# MyNixie.net
KiCad netlist of a schematic drawn in Altium Designer
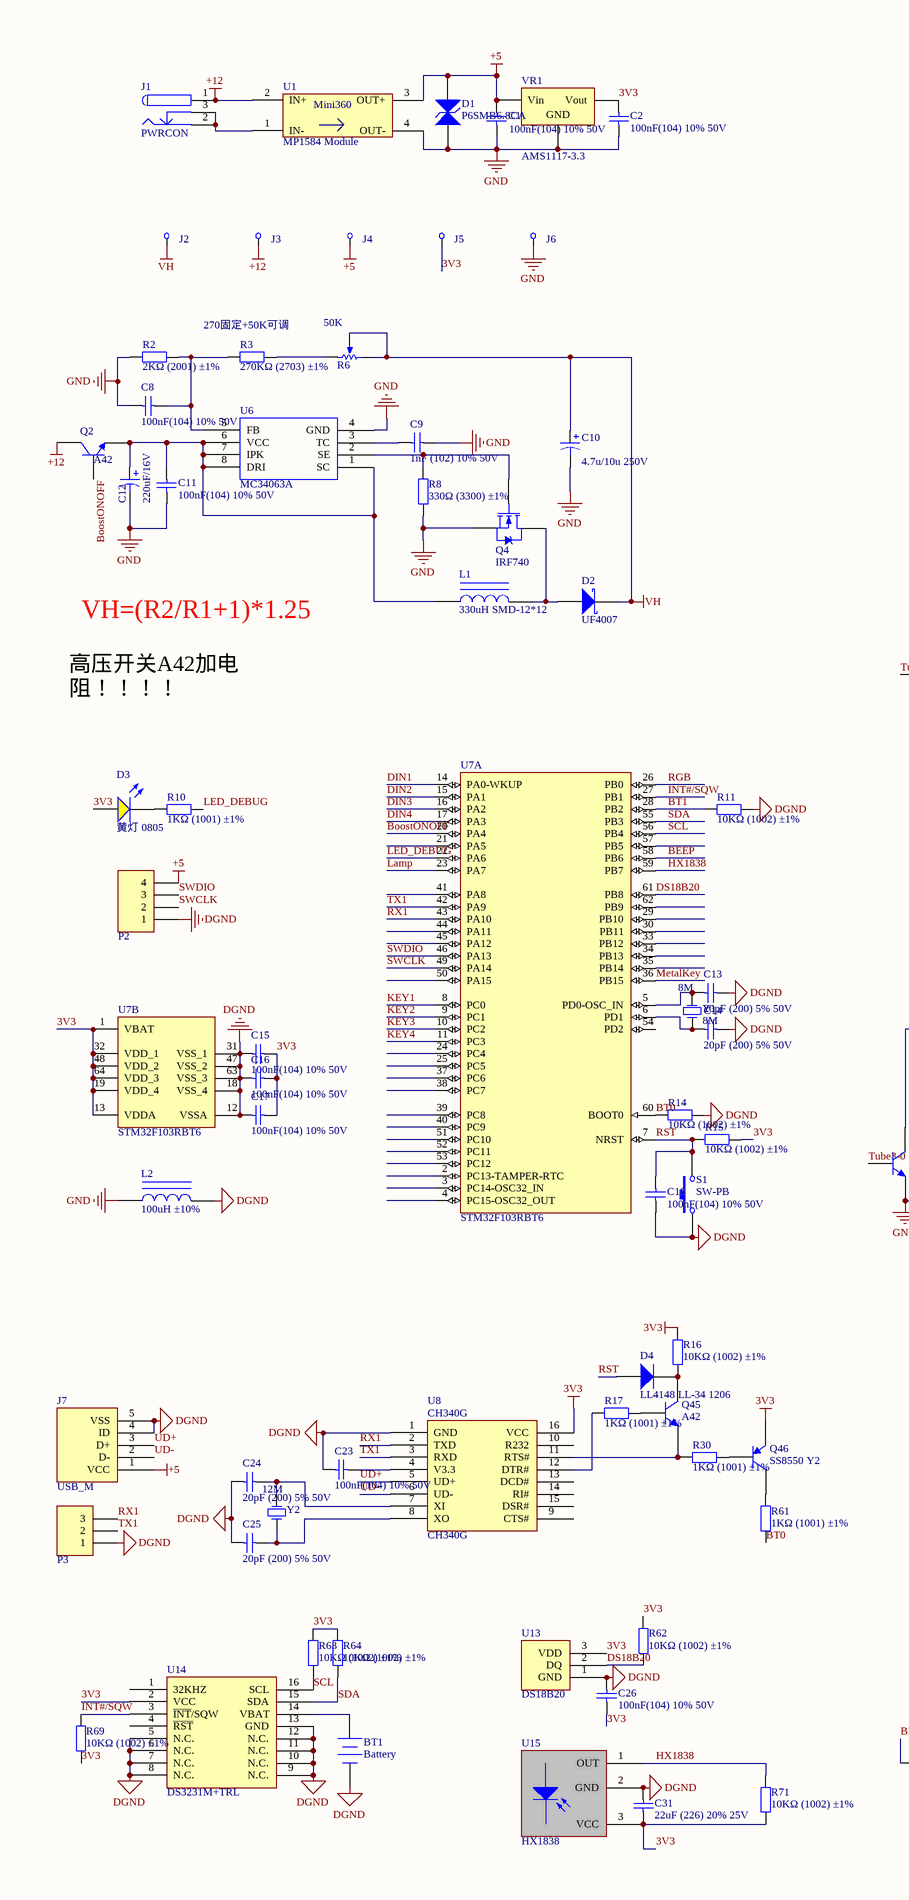
[diagram p0: MyNixie.SchDoc, left]
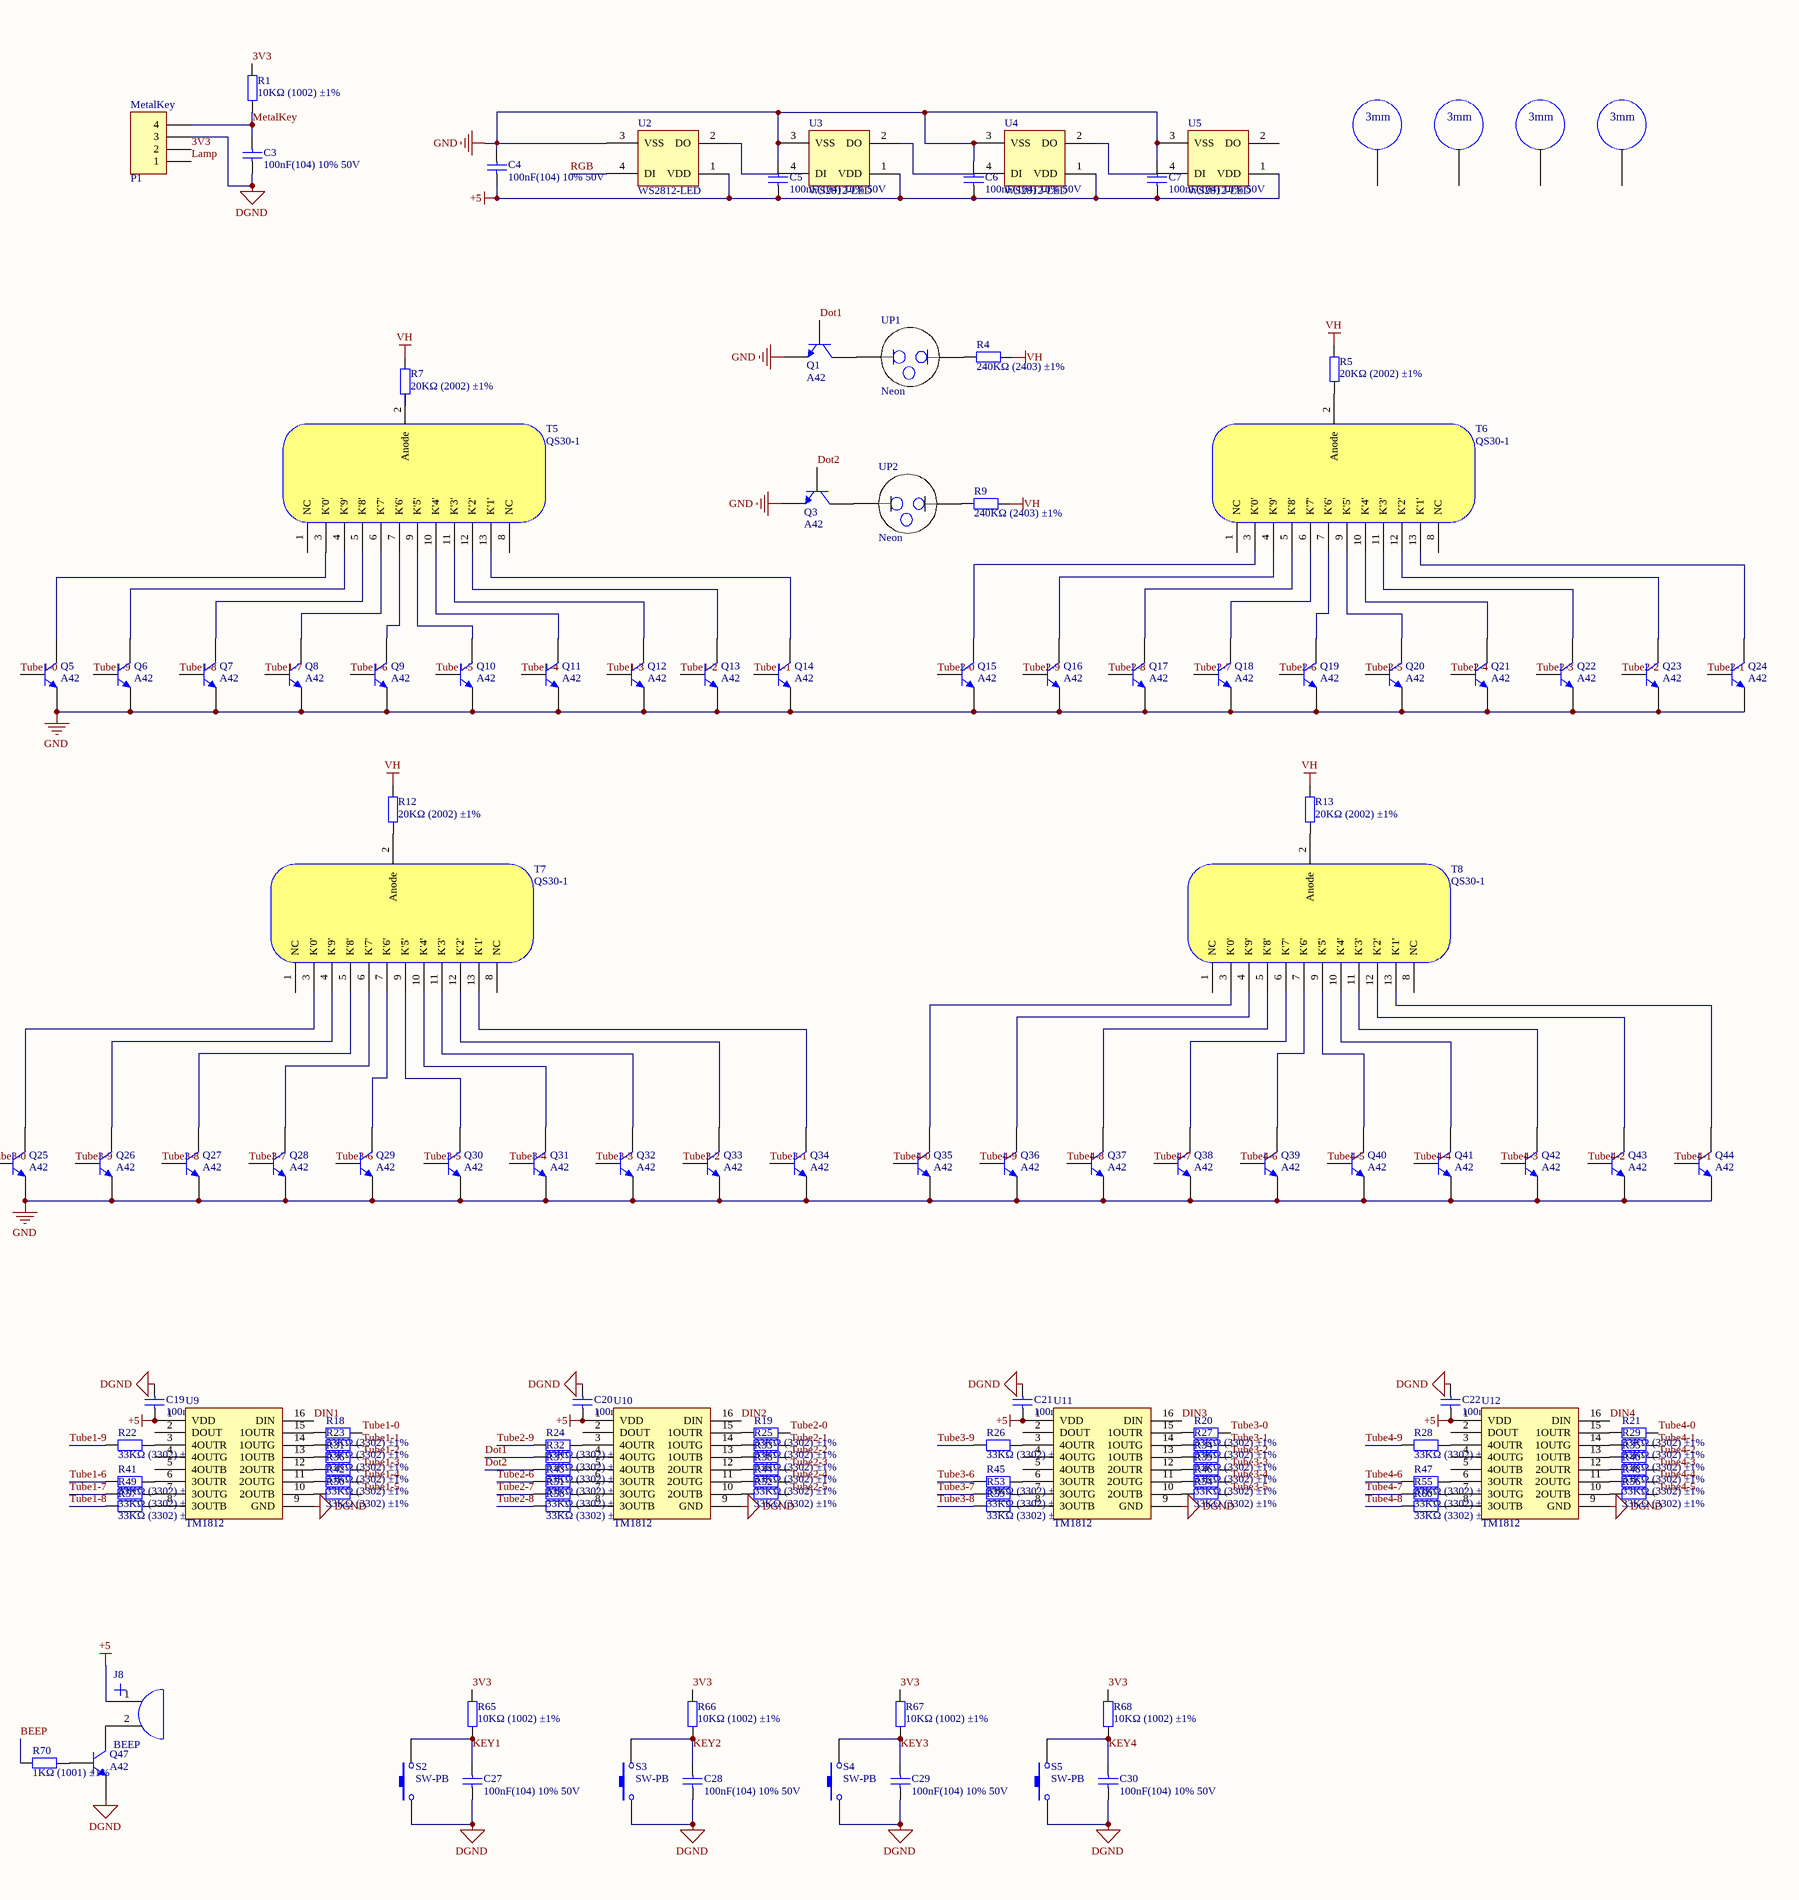
[diagram p1: MyNixie.SchDoc, right]

(export (version "E")
  (design (tool "Eeschema 10.0.6"))
  (components
    (comp (ref "BT1")
      (value "Battery")
      (footprint "CR2032")
      (description "备份电池")
      (fields (field (name "PUBLISHER") "Altium Limited"))
      (libsource (lib "fszhang") (part "Battery"))
    )
    (comp (ref "C1")
      (value "100nF(104) 10% 50V")
      (footprint "LC-0805_C")
      (description "贴片电容")
      (libsource (lib "Miscellaneous Devices LC") (part "0805 100nF(104) 10% 50V"))
    )
    (comp (ref "C2")
      (value "100nF(104) 10% 50V")
      (footprint "LC-0805_C")
      (description "贴片电容")
      (libsource (lib "Miscellaneous Devices LC") (part "0805 100nF(104) 10% 50V"))
    )
    (comp (ref "C3")
      (value "100nF(104) 10% 50V")
      (footprint "LC-0805_C")
      (description "贴片电容")
      (libsource (lib "Miscellaneous Devices LC") (part "0805 100nF(104) 10% 50V"))
    )
    (comp (ref "C4")
      (value "100nF(104) 10% 50V")
      (footprint "LC-0805_C")
      (description "贴片电容")
      (libsource (lib "Miscellaneous Devices LC") (part "0805 100nF(104) 10% 50V"))
    )
    (comp (ref "C5")
      (value "100nF(104) 10% 50V")
      (footprint "LC-0805_C")
      (description "贴片电容")
      (libsource (lib "Miscellaneous Devices LC") (part "0805 100nF(104) 10% 50V"))
    )
    (comp (ref "C6")
      (value "100nF(104) 10% 50V")
      (footprint "LC-0805_C")
      (description "贴片电容")
      (libsource (lib "Miscellaneous Devices LC") (part "0805 100nF(104) 10% 50V"))
    )
    (comp (ref "C7")
      (value "100nF(104) 10% 50V")
      (footprint "LC-0805_C")
      (description "贴片电容")
      (libsource (lib "Miscellaneous Devices LC") (part "0805 100nF(104) 10% 50V"))
    )
    (comp (ref "C8")
      (value "100nF(104) 10% 50V")
      (footprint "LC-0805_C")
      (description "贴片电容")
      (libsource (lib "Miscellaneous Devices LC") (part "0805 100nF(104) 10% 50V"))
    )
    (comp (ref "C9")
      (value "1nF (102) 10% 50V")
      (footprint "LC-0805_C")
      (description "贴片电容")
      (libsource (lib "Miscellaneous Devices LC") (part "0805 1nF (102) 10% 50V"))
    )
    (comp (ref "C10")
      (value "4.7u/10u 250V")
      (footprint "C-RB-8")
      (description "极性电解电容")
      (fields (field (name "PUBLISHER") "Altium Limited"))
      (libsource (lib "Miscellaneous Devices") (part "Cap Pol1"))
    )
    (comp (ref "C11")
      (value "100nF(104) 10% 50V")
      (footprint "LC-0805_C")
      (description "贴片电容")
      (libsource (lib "Miscellaneous Devices LC") (part "0805 100nF(104) 10% 50V"))
    )
    (comp (ref "C12")
      (value "220uF/16V")
      (footprint "C-RB-6")
      (description "极性电解电容")
      (fields (field (name "PUBLISHER") "Altium Limited"))
      (libsource (lib "Miscellaneous Devices") (part "Cap Pol1"))
    )
    (comp (ref "C13")
      (value "20pF (200) 5% 50V")
      (footprint "LC-0805_C")
      (description "贴片电容")
      (libsource (lib "Miscellaneous Devices LC") (part "0805 20pF (200) 5% 50V"))
    )
    (comp (ref "C14")
      (value "20pF (200) 5% 50V")
      (footprint "LC-0805_C")
      (description "贴片电容")
      (libsource (lib "Miscellaneous Devices LC") (part "0805 20pF (200) 5% 50V"))
    )
    (comp (ref "C15")
      (value "100nF(104) 10% 50V")
      (footprint "LC-0805_C")
      (description "贴片电容")
      (libsource (lib "Miscellaneous Devices LC") (part "0805 100nF(104) 10% 50V"))
    )
    (comp (ref "C16")
      (value "100nF(104) 10% 50V")
      (footprint "LC-0805_C")
      (description "贴片电容")
      (libsource (lib "Miscellaneous Devices LC") (part "0805 100nF(104) 10% 50V"))
    )
    (comp (ref "C17")
      (value "100nF(104) 10% 50V")
      (footprint "LC-0805_C")
      (description "贴片电容")
      (libsource (lib "Miscellaneous Devices LC") (part "0805 100nF(104) 10% 50V"))
    )
    (comp (ref "C18")
      (value "100nF(104) 10% 50V")
      (footprint "LC-0805_C")
      (description "贴片电容")
      (libsource (lib "Miscellaneous Devices LC") (part "0805 100nF(104) 10% 50V"))
    )
    (comp (ref "C19")
      (value "100nF(104) 10% 50V")
      (footprint "LC-0805_C")
      (description "贴片电容")
      (libsource (lib "Miscellaneous Devices LC") (part "0805 100nF(104) 10% 50V"))
    )
    (comp (ref "C20")
      (value "100nF(104) 10% 50V")
      (footprint "LC-0805_C")
      (description "贴片电容")
      (libsource (lib "Miscellaneous Devices LC") (part "0805 100nF(104) 10% 50V"))
    )
    (comp (ref "C21")
      (value "100nF(104) 10% 50V")
      (footprint "LC-0805_C")
      (description "贴片电容")
      (libsource (lib "Miscellaneous Devices LC") (part "0805 100nF(104) 10% 50V"))
    )
    (comp (ref "C22")
      (value "100nF(104) 10% 50V")
      (footprint "LC-0805_C")
      (description "贴片电容")
      (libsource (lib "Miscellaneous Devices LC") (part "0805 100nF(104) 10% 50V"))
    )
    (comp (ref "C23")
      (value "100nF(104) 10% 50V")
      (footprint "LC-0805_C")
      (description "贴片电容")
      (libsource (lib "Miscellaneous Devices LC") (part "0805 100nF(104) 10% 50V"))
    )
    (comp (ref "C24")
      (value "20pF (200) 5% 50V")
      (footprint "LC-0805_C")
      (description "贴片电容")
      (libsource (lib "Miscellaneous Devices LC") (part "0805 20pF (200) 5% 50V"))
    )
    (comp (ref "C25")
      (value "20pF (200) 5% 50V")
      (footprint "LC-0805_C")
      (description "贴片电容")
      (libsource (lib "Miscellaneous Devices LC") (part "0805 20pF (200) 5% 50V"))
    )
    (comp (ref "C26")
      (value "100nF(104) 10% 50V")
      (footprint "LC-0805_C")
      (description "贴片电容")
      (libsource (lib "Miscellaneous Devices LC") (part "0805 100nF(104) 10% 50V"))
    )
    (comp (ref "C27")
      (value "100nF(104) 10% 50V")
      (footprint "LC-0805_C")
      (description "贴片电容")
      (libsource (lib "Miscellaneous Devices LC") (part "0805 100nF(104) 10% 50V"))
    )
    (comp (ref "C28")
      (value "100nF(104) 10% 50V")
      (footprint "LC-0805_C")
      (description "贴片电容")
      (libsource (lib "Miscellaneous Devices LC") (part "0805 100nF(104) 10% 50V"))
    )
    (comp (ref "C29")
      (value "100nF(104) 10% 50V")
      (footprint "LC-0805_C")
      (description "贴片电容")
      (libsource (lib "Miscellaneous Devices LC") (part "0805 100nF(104) 10% 50V"))
    )
    (comp (ref "C30")
      (value "100nF(104) 10% 50V")
      (footprint "LC-0805_C")
      (description "贴片电容")
      (libsource (lib "Miscellaneous Devices LC") (part "0805 100nF(104) 10% 50V"))
    )
    (comp (ref "C31")
      (value "22uF (226) 20% 25V")
      (footprint "LC-0805_C")
      (description "贴片电容")
      (libsource (lib "Miscellaneous Devices LC") (part "0805 22uF (226) 20% 25V"))
    )
    (comp (ref "D1")
      (value "P6SMB6.8CA")
      (footprint "LC-SMB(DO-214AA)_S1")
      (description "TVS")
      (libsource (lib "Miscellaneous Devices LC") (part "SMB/DO-214AA P6SMB6.8CA"))
    )
    (comp (ref "D2")
      (value "UF4007")
      (footprint "DO-41")
      (description "Schottky Diode")
      (fields (field (name "PUBLISHER") "Altium Limited"))
      (libsource (lib "Miscellaneous Devices") (part "D Schottky"))
    )
    (comp (ref "D3")
      (value "黄灯 0805")
      (footprint "LC-0805_LED_S1")
      (description "发光二极管")
      (libsource (lib "Miscellaneous Devices LC") (part "0805 黄灯"))
    )
    (comp (ref "D4")
      (value "LL4148 LL-34 1206")
      (footprint "LC-LL-34")
      (description "开关二极管")
      (libsource (lib "Miscellaneous Devices LC") (part "LL-34 LL4148 LL-34 1206"))
    )
    (comp (ref "J1")
      (value "PWRCON")
      (footprint "DC-005")
      (description "直流电源端子")
      (fields (field (name "PUBLISHER") "Altium Limited"))
      (libsource (lib "fszhang") (part "PWRCON"))
    )
    (comp (ref "J2")
      (value "CHECK")
      (footprint "CHECK-B")
      (description "测试点")
      (libsource (lib "fszhang") (part "CHECK"))
    )
    (comp (ref "J3")
      (value "CHECK")
      (footprint "CHECK-B")
      (description "测试点")
      (libsource (lib "fszhang") (part "CHECK"))
    )
    (comp (ref "J4")
      (value "CHECK")
      (footprint "CHECK-B")
      (description "测试点")
      (libsource (lib "fszhang") (part "CHECK"))
    )
    (comp (ref "J5")
      (value "CHECK")
      (footprint "CHECK-B")
      (description "测试点")
      (libsource (lib "fszhang") (part "CHECK"))
    )
    (comp (ref "J6")
      (value "CHECK")
      (footprint "CHECK-B")
      (description "测试点")
      (libsource (lib "fszhang") (part "CHECK"))
    )
    (comp (ref "J7")
      (value "USB_M")
      (footprint "USB_MICRO")
      (description "MicroUSB接口")
      (libsource (lib "fszhang") (part "USB_M"))
    )
    (comp (ref "J8")
      (value "BEEP")
      (footprint "Beep")
      (description "蜂鸣器")
      (libsource (lib "fszhang") (part "BEEP"))
    )
    (comp (ref "L1")
      (value "330uH SMD-12*12")
      (footprint "L-SMD-12")
      (description "Magnetic-Core Inductor")
      (fields (field (name "PUBLISHER") "Altium Limited"))
      (libsource (lib "Miscellaneous Devices") (part "Inductor Iron"))
    )
    (comp (ref "L2")
      (value "100uH ±10%")
      (footprint "LC-0805_L")
      (description "贴片电感")
      (libsource (lib "Miscellaneous Devices LC") (part "0805 100uH 10%"))
    )
    (comp (ref "P1")
      (value "MetalKey")
      (footprint "HDR4X1_A")
      (description "接插件")
      (fields (field (name "PUBLISHER") "Altium Limited"))
      (libsource (lib "fszhang") (part "Header 4"))
    )
    (comp (ref "P2")
      (value "Header 4")
      (footprint "HDR4X1_A")
      (description "接插件")
      (fields (field (name "PUBLISHER") "Altium Limited"))
      (libsource (lib "fszhang") (part "Header 4"))
    )
    (comp (ref "P3")
      (value "Header 3")
      (footprint "HDR3X1_A")
      (description "接插件")
      (fields (field (name "PUBLISHER") "Altium Limited"))
      (libsource (lib "fszhang") (part "Header 3"))
    )
    (comp (ref "Q1")
      (value "A42")
      (footprint "LC-SOT-23(SOT-23-3)")
      (description "三极管")
      (libsource (lib "Miscellaneous Devices LC") (part "SOT-23 SS8050 Y1"))
    )
    (comp (ref "Q2")
      (value "A42")
      (footprint "LC-SOT-23(SOT-23-3)")
      (description "三极管")
      (libsource (lib "Miscellaneous Devices LC") (part "SOT-23 SS8050 Y1"))
    )
    (comp (ref "Q3")
      (value "A42")
      (footprint "LC-SOT-23(SOT-23-3)")
      (description "三极管")
      (libsource (lib "Miscellaneous Devices LC") (part "SOT-23 SS8050 Y1"))
    )
    (comp (ref "Q4")
      (value "IRF740")
      (footprint "TO-220AB")
      (description "N-Channel Power MOSFET")
      (fields (field (name "PUBLISHER") "Altium Limited"))
      (libsource (lib "Miscellaneous Devices") (part "NMOS-2"))
    )
    (comp (ref "Q5")
      (value "A42")
      (footprint "LC-SOT-23(SOT-23-3)")
      (description "三极管")
      (libsource (lib "Miscellaneous Devices LC") (part "SOT-23 SS8050 Y1"))
    )
    (comp (ref "Q6")
      (value "A42")
      (footprint "LC-SOT-23(SOT-23-3)")
      (description "三极管")
      (libsource (lib "Miscellaneous Devices LC") (part "SOT-23 SS8050 Y1"))
    )
    (comp (ref "Q7")
      (value "A42")
      (footprint "LC-SOT-23(SOT-23-3)")
      (description "三极管")
      (libsource (lib "Miscellaneous Devices LC") (part "SOT-23 SS8050 Y1"))
    )
    (comp (ref "Q8")
      (value "A42")
      (footprint "LC-SOT-23(SOT-23-3)")
      (description "三极管")
      (libsource (lib "Miscellaneous Devices LC") (part "SOT-23 SS8050 Y1"))
    )
    (comp (ref "Q9")
      (value "A42")
      (footprint "LC-SOT-23(SOT-23-3)")
      (description "三极管")
      (libsource (lib "Miscellaneous Devices LC") (part "SOT-23 SS8050 Y1"))
    )
    (comp (ref "Q10")
      (value "A42")
      (footprint "LC-SOT-23(SOT-23-3)")
      (description "三极管")
      (libsource (lib "Miscellaneous Devices LC") (part "SOT-23 SS8050 Y1"))
    )
    (comp (ref "Q11")
      (value "A42")
      (footprint "LC-SOT-23(SOT-23-3)")
      (description "三极管")
      (libsource (lib "Miscellaneous Devices LC") (part "SOT-23 SS8050 Y1"))
    )
    (comp (ref "Q12")
      (value "A42")
      (footprint "LC-SOT-23(SOT-23-3)")
      (description "三极管")
      (libsource (lib "Miscellaneous Devices LC") (part "SOT-23 SS8050 Y1"))
    )
    (comp (ref "Q13")
      (value "A42")
      (footprint "LC-SOT-23(SOT-23-3)")
      (description "三极管")
      (libsource (lib "Miscellaneous Devices LC") (part "SOT-23 SS8050 Y1"))
    )
    (comp (ref "Q14")
      (value "A42")
      (footprint "LC-SOT-23(SOT-23-3)")
      (description "三极管")
      (libsource (lib "Miscellaneous Devices LC") (part "SOT-23 SS8050 Y1"))
    )
    (comp (ref "Q15")
      (value "A42")
      (footprint "LC-SOT-23(SOT-23-3)")
      (description "三极管")
      (libsource (lib "Miscellaneous Devices LC") (part "SOT-23 SS8050 Y1"))
    )
    (comp (ref "Q16")
      (value "A42")
      (footprint "LC-SOT-23(SOT-23-3)")
      (description "三极管")
      (libsource (lib "Miscellaneous Devices LC") (part "SOT-23 SS8050 Y1"))
    )
    (comp (ref "Q17")
      (value "A42")
      (footprint "LC-SOT-23(SOT-23-3)")
      (description "三极管")
      (libsource (lib "Miscellaneous Devices LC") (part "SOT-23 SS8050 Y1"))
    )
    (comp (ref "Q18")
      (value "A42")
      (footprint "LC-SOT-23(SOT-23-3)")
      (description "三极管")
      (libsource (lib "Miscellaneous Devices LC") (part "SOT-23 SS8050 Y1"))
    )
    (comp (ref "Q19")
      (value "A42")
      (footprint "LC-SOT-23(SOT-23-3)")
      (description "三极管")
      (libsource (lib "Miscellaneous Devices LC") (part "SOT-23 SS8050 Y1"))
    )
    (comp (ref "Q20")
      (value "A42")
      (footprint "LC-SOT-23(SOT-23-3)")
      (description "三极管")
      (libsource (lib "Miscellaneous Devices LC") (part "SOT-23 SS8050 Y1"))
    )
    (comp (ref "Q21")
      (value "A42")
      (footprint "LC-SOT-23(SOT-23-3)")
      (description "三极管")
      (libsource (lib "Miscellaneous Devices LC") (part "SOT-23 SS8050 Y1"))
    )
    (comp (ref "Q22")
      (value "A42")
      (footprint "LC-SOT-23(SOT-23-3)")
      (description "三极管")
      (libsource (lib "Miscellaneous Devices LC") (part "SOT-23 SS8050 Y1"))
    )
    (comp (ref "Q23")
      (value "A42")
      (footprint "LC-SOT-23(SOT-23-3)")
      (description "三极管")
      (libsource (lib "Miscellaneous Devices LC") (part "SOT-23 SS8050 Y1"))
    )
    (comp (ref "Q24")
      (value "A42")
      (footprint "LC-SOT-23(SOT-23-3)")
      (description "三极管")
      (libsource (lib "Miscellaneous Devices LC") (part "SOT-23 SS8050 Y1"))
    )
    (comp (ref "Q25")
      (value "A42")
      (footprint "LC-SOT-23(SOT-23-3)")
      (description "三极管")
      (libsource (lib "Miscellaneous Devices LC") (part "SOT-23 SS8050 Y1"))
    )
    (comp (ref "Q26")
      (value "A42")
      (footprint "LC-SOT-23(SOT-23-3)")
      (description "三极管")
      (libsource (lib "Miscellaneous Devices LC") (part "SOT-23 SS8050 Y1"))
    )
    (comp (ref "Q27")
      (value "A42")
      (footprint "LC-SOT-23(SOT-23-3)")
      (description "三极管")
      (libsource (lib "Miscellaneous Devices LC") (part "SOT-23 SS8050 Y1"))
    )
    (comp (ref "Q28")
      (value "A42")
      (footprint "LC-SOT-23(SOT-23-3)")
      (description "三极管")
      (libsource (lib "Miscellaneous Devices LC") (part "SOT-23 SS8050 Y1"))
    )
    (comp (ref "Q29")
      (value "A42")
      (footprint "LC-SOT-23(SOT-23-3)")
      (description "三极管")
      (libsource (lib "Miscellaneous Devices LC") (part "SOT-23 SS8050 Y1"))
    )
    (comp (ref "Q30")
      (value "A42")
      (footprint "LC-SOT-23(SOT-23-3)")
      (description "三极管")
      (libsource (lib "Miscellaneous Devices LC") (part "SOT-23 SS8050 Y1"))
    )
    (comp (ref "Q31")
      (value "A42")
      (footprint "LC-SOT-23(SOT-23-3)")
      (description "三极管")
      (libsource (lib "Miscellaneous Devices LC") (part "SOT-23 SS8050 Y1"))
    )
    (comp (ref "Q32")
      (value "A42")
      (footprint "LC-SOT-23(SOT-23-3)")
      (description "三极管")
      (libsource (lib "Miscellaneous Devices LC") (part "SOT-23 SS8050 Y1"))
    )
    (comp (ref "Q33")
      (value "A42")
      (footprint "LC-SOT-23(SOT-23-3)")
      (description "三极管")
      (libsource (lib "Miscellaneous Devices LC") (part "SOT-23 SS8050 Y1"))
    )
    (comp (ref "Q34")
      (value "A42")
      (footprint "LC-SOT-23(SOT-23-3)")
      (description "三极管")
      (libsource (lib "Miscellaneous Devices LC") (part "SOT-23 SS8050 Y1"))
    )
    (comp (ref "Q35")
      (value "A42")
      (footprint "LC-SOT-23(SOT-23-3)")
      (description "三极管")
      (libsource (lib "Miscellaneous Devices LC") (part "SOT-23 SS8050 Y1"))
    )
    (comp (ref "Q36")
      (value "A42")
      (footprint "LC-SOT-23(SOT-23-3)")
      (description "三极管")
      (libsource (lib "Miscellaneous Devices LC") (part "SOT-23 SS8050 Y1"))
    )
    (comp (ref "Q37")
      (value "A42")
      (footprint "LC-SOT-23(SOT-23-3)")
      (description "三极管")
      (libsource (lib "Miscellaneous Devices LC") (part "SOT-23 SS8050 Y1"))
    )
    (comp (ref "Q38")
      (value "A42")
      (footprint "LC-SOT-23(SOT-23-3)")
      (description "三极管")
      (libsource (lib "Miscellaneous Devices LC") (part "SOT-23 SS8050 Y1"))
    )
    (comp (ref "Q39")
      (value "A42")
      (footprint "LC-SOT-23(SOT-23-3)")
      (description "三极管")
      (libsource (lib "Miscellaneous Devices LC") (part "SOT-23 SS8050 Y1"))
    )
    (comp (ref "Q40")
      (value "A42")
      (footprint "LC-SOT-23(SOT-23-3)")
      (description "三极管")
      (libsource (lib "Miscellaneous Devices LC") (part "SOT-23 SS8050 Y1"))
    )
    (comp (ref "Q41")
      (value "A42")
      (footprint "LC-SOT-23(SOT-23-3)")
      (description "三极管")
      (libsource (lib "Miscellaneous Devices LC") (part "SOT-23 SS8050 Y1"))
    )
    (comp (ref "Q42")
      (value "A42")
      (footprint "LC-SOT-23(SOT-23-3)")
      (description "三极管")
      (libsource (lib "Miscellaneous Devices LC") (part "SOT-23 SS8050 Y1"))
    )
    (comp (ref "Q43")
      (value "A42")
      (footprint "LC-SOT-23(SOT-23-3)")
      (description "三极管")
      (libsource (lib "Miscellaneous Devices LC") (part "SOT-23 SS8050 Y1"))
    )
    (comp (ref "Q44")
      (value "A42")
      (footprint "LC-SOT-23(SOT-23-3)")
      (description "三极管")
      (libsource (lib "Miscellaneous Devices LC") (part "SOT-23 SS8050 Y1"))
    )
    (comp (ref "Q45")
      (value "A42")
      (footprint "LC-SOT-23(SOT-23-3)")
      (description "三极管")
      (libsource (lib "Miscellaneous Devices LC") (part "SOT-23 SS8050 Y1"))
    )
    (comp (ref "Q46")
      (value "SS8550 Y2")
      (footprint "LC-SOT-23(SOT-23-3)")
      (description "三极管")
      (libsource (lib "Miscellaneous Devices LC") (part "SOT-23 SS8550 Y2"))
    )
    (comp (ref "Q47")
      (value "A42")
      (footprint "LC-SOT-23(SOT-23-3)")
      (description "三极管")
      (libsource (lib "Miscellaneous Devices LC") (part "SOT-23 SS8050 Y1"))
    )
    (comp (ref "R1")
      (value "10KΩ (1002) ±1%")
      (footprint "LC-0805_R")
      (description "贴片电阻")
      (libsource (lib "") (part "0805 10KΩ (1002) 1%_2"))
    )
    (comp (ref "R2")
      (value "2KΩ (2001) ±1%")
      (footprint "LC-0805_R")
      (description "贴片电阻")
      (libsource (lib "Miscellaneous Devices LC") (part "0805 2KΩ (2001) 1%"))
    )
    (comp (ref "R3")
      (value "270KΩ (2703) ±1%")
      (footprint "LC-0805_R")
      (description "贴片电阻")
      (libsource (lib "Miscellaneous Devices LC") (part "0805 270KΩ (2703) 1%"))
    )
    (comp (ref "R4")
      (value "240KΩ (2403) ±1%")
      (footprint "LC-0805_R")
      (description "贴片电阻")
      (libsource (lib "Miscellaneous Devices LC") (part "0805 240KΩ (2403) 1%"))
    )
    (comp (ref "R5")
      (value "20KΩ (2002) ±1%")
      (footprint "LC-0805_R")
      (description "贴片电阻")
      (libsource (lib "Miscellaneous Devices LC") (part "0805 20KΩ (2002) 1%"))
    )
    (comp (ref "R6")
      (value "50K")
      (footprint "VR_B1")
      (description "精密可调电阻")
      (fields (field (name "PUBLISHER") "Altium Limited"))
      (libsource (lib "fszhang") (part "RES-RPot"))
    )
    (comp (ref "R7")
      (value "20KΩ (2002) ±1%")
      (footprint "LC-0805_R")
      (description "贴片电阻")
      (libsource (lib "Miscellaneous Devices LC") (part "0805 20KΩ (2002) 1%"))
    )
    (comp (ref "R8")
      (value "330Ω (3300) ±1%")
      (footprint "LC-0805_R")
      (description "贴片电阻")
      (libsource (lib "Miscellaneous Devices LC") (part "0805 330Ω (3300) 1%"))
    )
    (comp (ref "R9")
      (value "240KΩ (2403) ±1%")
      (footprint "LC-0805_R")
      (description "贴片电阻")
      (libsource (lib "Miscellaneous Devices LC") (part "0805 240KΩ (2403) 1%"))
    )
    (comp (ref "R10")
      (value "1KΩ (1001) ±1%")
      (footprint "LC-0805_R")
      (description "贴片电阻")
      (libsource (lib "") (part "0805 1KΩ (1001) 1%_1"))
    )
    (comp (ref "R11")
      (value "10KΩ (1002) ±1%")
      (footprint "LC-0805_R")
      (description "贴片电阻")
      (libsource (lib "Miscellaneous Devices LC") (part "0805 10KΩ (1002) 1%"))
    )
    (comp (ref "R12")
      (value "20KΩ (2002) ±1%")
      (footprint "LC-0805_R")
      (description "贴片电阻")
      (libsource (lib "Miscellaneous Devices LC") (part "0805 20KΩ (2002) 1%"))
    )
    (comp (ref "R13")
      (value "20KΩ (2002) ±1%")
      (footprint "LC-0805_R")
      (description "贴片电阻")
      (libsource (lib "Miscellaneous Devices LC") (part "0805 20KΩ (2002) 1%"))
    )
    (comp (ref "R14")
      (value "10KΩ (1002) ±1%")
      (footprint "LC-0805_R")
      (description "贴片电阻")
      (libsource (lib "Miscellaneous Devices LC") (part "0805 10KΩ (1002) 1%"))
    )
    (comp (ref "R15")
      (value "10KΩ (1002) ±1%")
      (footprint "LC-0805_R")
      (description "贴片电阻")
      (libsource (lib "Miscellaneous Devices LC") (part "0805 10KΩ (1002) 1%"))
    )
    (comp (ref "R16")
      (value "10KΩ (1002) ±1%")
      (footprint "LC-0805_R")
      (description "贴片电阻")
      (libsource (lib "") (part "0805 10KΩ (1002) 1%_1"))
    )
    (comp (ref "R17")
      (value "1KΩ (1001) ±1%")
      (footprint "LC-0805_R")
      (description "贴片电阻")
      (libsource (lib "") (part "0805 1KΩ (1001) 1%_1"))
    )
    (comp (ref "R18")
      (value "33KΩ (3302) ±1%")
      (footprint "LC-0805_R")
      (description "贴片电阻")
      (libsource (lib "Miscellaneous Devices LC") (part "0805 33KΩ (3302) 1%"))
    )
    (comp (ref "R19")
      (value "33KΩ (3302) ±1%")
      (footprint "LC-0805_R")
      (description "贴片电阻")
      (libsource (lib "Miscellaneous Devices LC") (part "0805 33KΩ (3302) 1%"))
    )
    (comp (ref "R20")
      (value "33KΩ (3302) ±1%")
      (footprint "LC-0805_R")
      (description "贴片电阻")
      (libsource (lib "Miscellaneous Devices LC") (part "0805 33KΩ (3302) 1%"))
    )
    (comp (ref "R21")
      (value "33KΩ (3302) ±1%")
      (footprint "LC-0805_R")
      (description "贴片电阻")
      (libsource (lib "Miscellaneous Devices LC") (part "0805 33KΩ (3302) 1%"))
    )
    (comp (ref "R22")
      (value "33KΩ (3302) ±1%")
      (footprint "LC-0805_R")
      (description "贴片电阻")
      (libsource (lib "Miscellaneous Devices LC") (part "0805 33KΩ (3302) 1%"))
    )
    (comp (ref "R23")
      (value "33KΩ (3302) ±1%")
      (footprint "LC-0805_R")
      (description "贴片电阻")
      (libsource (lib "Miscellaneous Devices LC") (part "0805 33KΩ (3302) 1%"))
    )
    (comp (ref "R24")
      (value "33KΩ (3302) ±1%")
      (footprint "LC-0805_R")
      (description "贴片电阻")
      (libsource (lib "Miscellaneous Devices LC") (part "0805 33KΩ (3302) 1%"))
    )
    (comp (ref "R25")
      (value "33KΩ (3302) ±1%")
      (footprint "LC-0805_R")
      (description "贴片电阻")
      (libsource (lib "Miscellaneous Devices LC") (part "0805 33KΩ (3302) 1%"))
    )
    (comp (ref "R26")
      (value "33KΩ (3302) ±1%")
      (footprint "LC-0805_R")
      (description "贴片电阻")
      (libsource (lib "Miscellaneous Devices LC") (part "0805 33KΩ (3302) 1%"))
    )
    (comp (ref "R27")
      (value "33KΩ (3302) ±1%")
      (footprint "LC-0805_R")
      (description "贴片电阻")
      (libsource (lib "Miscellaneous Devices LC") (part "0805 33KΩ (3302) 1%"))
    )
    (comp (ref "R28")
      (value "33KΩ (3302) ±1%")
      (footprint "LC-0805_R")
      (description "贴片电阻")
      (libsource (lib "Miscellaneous Devices LC") (part "0805 33KΩ (3302) 1%"))
    )
    (comp (ref "R29")
      (value "33KΩ (3302) ±1%")
      (footprint "LC-0805_R")
      (description "贴片电阻")
      (libsource (lib "Miscellaneous Devices LC") (part "0805 33KΩ (3302) 1%"))
    )
    (comp (ref "R30")
      (value "1KΩ (1001) ±1%")
      (footprint "LC-0805_R")
      (description "贴片电阻")
      (libsource (lib "") (part "0805 1KΩ (1001) 1%_1"))
    )
    (comp (ref "R31")
      (value "33KΩ (3302) ±1%")
      (footprint "LC-0805_R")
      (description "贴片电阻")
      (libsource (lib "Miscellaneous Devices LC") (part "0805 33KΩ (3302) 1%"))
    )
    (comp (ref "R32")
      (value "33KΩ (3302) ±1%")
      (footprint "LC-0805_R")
      (description "贴片电阻")
      (libsource (lib "Miscellaneous Devices LC") (part "0805 33KΩ (3302) 1%"))
    )
    (comp (ref "R33")
      (value "33KΩ (3302) ±1%")
      (footprint "LC-0805_R")
      (description "贴片电阻")
      (libsource (lib "Miscellaneous Devices LC") (part "0805 33KΩ (3302) 1%"))
    )
    (comp (ref "R34")
      (value "33KΩ (3302) ±1%")
      (footprint "LC-0805_R")
      (description "贴片电阻")
      (libsource (lib "Miscellaneous Devices LC") (part "0805 33KΩ (3302) 1%"))
    )
    (comp (ref "R35")
      (value "33KΩ (3302) ±1%")
      (footprint "LC-0805_R")
      (description "贴片电阻")
      (libsource (lib "Miscellaneous Devices LC") (part "0805 33KΩ (3302) 1%"))
    )
    (comp (ref "R36")
      (value "33KΩ (3302) ±1%")
      (footprint "LC-0805_R")
      (description "贴片电阻")
      (libsource (lib "Miscellaneous Devices LC") (part "0805 33KΩ (3302) 1%"))
    )
    (comp (ref "R37")
      (value "33KΩ (3302) ±1%")
      (footprint "LC-0805_R")
      (description "贴片电阻")
      (libsource (lib "Miscellaneous Devices LC") (part "0805 33KΩ (3302) 1%"))
    )
    (comp (ref "R38")
      (value "33KΩ (3302) ±1%")
      (footprint "LC-0805_R")
      (description "贴片电阻")
      (libsource (lib "Miscellaneous Devices LC") (part "0805 33KΩ (3302) 1%"))
    )
    (comp (ref "R39")
      (value "33KΩ (3302) ±1%")
      (footprint "LC-0805_R")
      (description "贴片电阻")
      (libsource (lib "Miscellaneous Devices LC") (part "0805 33KΩ (3302) 1%"))
    )
    (comp (ref "R40")
      (value "33KΩ (3302) ±1%")
      (footprint "LC-0805_R")
      (description "贴片电阻")
      (libsource (lib "Miscellaneous Devices LC") (part "0805 33KΩ (3302) 1%"))
    )
    (comp (ref "R41")
      (value "33KΩ (3302) ±1%")
      (footprint "LC-0805_R")
      (description "贴片电阻")
      (libsource (lib "Miscellaneous Devices LC") (part "0805 33KΩ (3302) 1%"))
    )
    (comp (ref "R42")
      (value "33KΩ (3302) ±1%")
      (footprint "LC-0805_R")
      (description "贴片电阻")
      (libsource (lib "Miscellaneous Devices LC") (part "0805 33KΩ (3302) 1%"))
    )
    (comp (ref "R43")
      (value "33KΩ (3302) ±1%")
      (footprint "LC-0805_R")
      (description "贴片电阻")
      (libsource (lib "Miscellaneous Devices LC") (part "0805 33KΩ (3302) 1%"))
    )
    (comp (ref "R44")
      (value "33KΩ (3302) ±1%")
      (footprint "LC-0805_R")
      (description "贴片电阻")
      (libsource (lib "Miscellaneous Devices LC") (part "0805 33KΩ (3302) 1%"))
    )
    (comp (ref "R45")
      (value "33KΩ (3302) ±1%")
      (footprint "LC-0805_R")
      (description "贴片电阻")
      (libsource (lib "Miscellaneous Devices LC") (part "0805 33KΩ (3302) 1%"))
    )
    (comp (ref "R46")
      (value "33KΩ (3302) ±1%")
      (footprint "LC-0805_R")
      (description "贴片电阻")
      (libsource (lib "Miscellaneous Devices LC") (part "0805 33KΩ (3302) 1%"))
    )
    (comp (ref "R47")
      (value "33KΩ (3302) ±1%")
      (footprint "LC-0805_R")
      (description "贴片电阻")
      (libsource (lib "Miscellaneous Devices LC") (part "0805 33KΩ (3302) 1%"))
    )
    (comp (ref "R48")
      (value "33KΩ (3302) ±1%")
      (footprint "LC-0805_R")
      (description "贴片电阻")
      (libsource (lib "Miscellaneous Devices LC") (part "0805 33KΩ (3302) 1%"))
    )
    (comp (ref "R49")
      (value "33KΩ (3302) ±1%")
      (footprint "LC-0805_R")
      (description "贴片电阻")
      (libsource (lib "Miscellaneous Devices LC") (part "0805 33KΩ (3302) 1%"))
    )
    (comp (ref "R50")
      (value "33KΩ (3302) ±1%")
      (footprint "LC-0805_R")
      (description "贴片电阻")
      (libsource (lib "Miscellaneous Devices LC") (part "0805 33KΩ (3302) 1%"))
    )
    (comp (ref "R51")
      (value "33KΩ (3302) ±1%")
      (footprint "LC-0805_R")
      (description "贴片电阻")
      (libsource (lib "Miscellaneous Devices LC") (part "0805 33KΩ (3302) 1%"))
    )
    (comp (ref "R52")
      (value "33KΩ (3302) ±1%")
      (footprint "LC-0805_R")
      (description "贴片电阻")
      (libsource (lib "Miscellaneous Devices LC") (part "0805 33KΩ (3302) 1%"))
    )
    (comp (ref "R53")
      (value "33KΩ (3302) ±1%")
      (footprint "LC-0805_R")
      (description "贴片电阻")
      (libsource (lib "Miscellaneous Devices LC") (part "0805 33KΩ (3302) 1%"))
    )
    (comp (ref "R54")
      (value "33KΩ (3302) ±1%")
      (footprint "LC-0805_R")
      (description "贴片电阻")
      (libsource (lib "Miscellaneous Devices LC") (part "0805 33KΩ (3302) 1%"))
    )
    (comp (ref "R55")
      (value "33KΩ (3302) ±1%")
      (footprint "LC-0805_R")
      (description "贴片电阻")
      (libsource (lib "Miscellaneous Devices LC") (part "0805 33KΩ (3302) 1%"))
    )
    (comp (ref "R56")
      (value "33KΩ (3302) ±1%")
      (footprint "LC-0805_R")
      (description "贴片电阻")
      (libsource (lib "Miscellaneous Devices LC") (part "0805 33KΩ (3302) 1%"))
    )
    (comp (ref "R57")
      (value "33KΩ (3302) ±1%")
      (footprint "LC-0805_R")
      (description "贴片电阻")
      (libsource (lib "Miscellaneous Devices LC") (part "0805 33KΩ (3302) 1%"))
    )
    (comp (ref "R58")
      (value "33KΩ (3302) ±1%")
      (footprint "LC-0805_R")
      (description "贴片电阻")
      (libsource (lib "Miscellaneous Devices LC") (part "0805 33KΩ (3302) 1%"))
    )
    (comp (ref "R59")
      (value "33KΩ (3302) ±1%")
      (footprint "LC-0805_R")
      (description "贴片电阻")
      (libsource (lib "Miscellaneous Devices LC") (part "0805 33KΩ (3302) 1%"))
    )
    (comp (ref "R60")
      (value "33KΩ (3302) ±1%")
      (footprint "LC-0805_R")
      (description "贴片电阻")
      (libsource (lib "Miscellaneous Devices LC") (part "0805 33KΩ (3302) 1%"))
    )
    (comp (ref "R61")
      (value "1KΩ (1001) ±1%")
      (footprint "LC-0805_R")
      (description "贴片电阻")
      (libsource (lib "Miscellaneous Devices LC") (part "0805 1KΩ (1001) 1%"))
    )
    (comp (ref "R62")
      (value "10KΩ (1002) ±1%")
      (footprint "LC-0805_R")
      (description "贴片电阻")
      (libsource (lib "Miscellaneous Devices LC") (part "0805 10KΩ (1002) 1%"))
    )
    (comp (ref "R63")
      (value "10KΩ (1002) ±1%")
      (footprint "LC-0805_R")
      (description "贴片电阻")
      (libsource (lib "Miscellaneous Devices LC") (part "0805 10KΩ (1002) 1%"))
    )
    (comp (ref "R64")
      (value "10KΩ (1002) ±1%")
      (footprint "LC-0805_R")
      (description "贴片电阻")
      (libsource (lib "Miscellaneous Devices LC") (part "0805 10KΩ (1002) 1%"))
    )
    (comp (ref "R65")
      (value "10KΩ (1002) ±1%")
      (footprint "LC-0805_R")
      (description "贴片电阻")
      (libsource (lib "") (part "0805 10KΩ (1002) 1%_2"))
    )
    (comp (ref "R66")
      (value "10KΩ (1002) ±1%")
      (footprint "LC-0805_R")
      (description "贴片电阻")
      (libsource (lib "") (part "0805 10KΩ (1002) 1%_2"))
    )
    (comp (ref "R67")
      (value "10KΩ (1002) ±1%")
      (footprint "LC-0805_R")
      (description "贴片电阻")
      (libsource (lib "") (part "0805 10KΩ (1002) 1%_2"))
    )
    (comp (ref "R68")
      (value "10KΩ (1002) ±1%")
      (footprint "LC-0805_R")
      (description "贴片电阻")
      (libsource (lib "") (part "0805 10KΩ (1002) 1%_2"))
    )
    (comp (ref "R69")
      (value "10KΩ (1002) ±1%")
      (footprint "LC-0805_R")
      (description "贴片电阻")
      (libsource (lib "Miscellaneous Devices LC") (part "0805 10KΩ (1002) 1%"))
    )
    (comp (ref "R70")
      (value "1KΩ (1001) ±1%")
      (footprint "LC-0805_R")
      (description "贴片电阻")
      (libsource (lib "") (part "0805 1KΩ (1001) 1%_1"))
    )
    (comp (ref "R71")
      (value "10KΩ (1002) ±1%")
      (footprint "LC-0805_R")
      (description "贴片电阻")
      (libsource (lib "Miscellaneous Devices LC") (part "0805 10KΩ (1002) 1%"))
    )
    (comp (ref "S1")
      (value "SW-PB")
      (footprint "SW_PB2_A1")
      (description "微动开关")
      (fields (field (name "PUBLISHER") "Altium Limited"))
      (libsource (lib "fszhang") (part "SW-PB"))
    )
    (comp (ref "S2")
      (value "SW-PB")
      (footprint "SW_PB2_A1")
      (description "微动开关")
      (fields (field (name "PUBLISHER") "Altium Limited"))
      (libsource (lib "fszhang") (part "SW-PB"))
    )
    (comp (ref "S3")
      (value "SW-PB")
      (footprint "SW_PB2_A1")
      (description "微动开关")
      (fields (field (name "PUBLISHER") "Altium Limited"))
      (libsource (lib "fszhang") (part "SW-PB"))
    )
    (comp (ref "S4")
      (value "SW-PB")
      (footprint "SW_PB2_A1")
      (description "微动开关")
      (fields (field (name "PUBLISHER") "Altium Limited"))
      (libsource (lib "fszhang") (part "SW-PB"))
    )
    (comp (ref "S5")
      (value "SW-PB")
      (footprint "SW_PB2_A1")
      (description "微动开关")
      (fields (field (name "PUBLISHER") "Altium Limited"))
      (libsource (lib "fszhang") (part "SW-PB"))
    )
    (comp (ref "T1") (value "M3铜柱螺丝孔") (footprint "螺丝孔-3mm") (libsource (lib "fszhang") (part "M3铜柱螺丝孔")))
    (comp (ref "T2") (value "M3铜柱螺丝孔") (footprint "螺丝孔-3mm") (libsource (lib "fszhang") (part "M3铜柱螺丝孔")))
    (comp (ref "T3") (value "M3铜柱螺丝孔") (footprint "螺丝孔-3mm") (libsource (lib "fszhang") (part "M3铜柱螺丝孔")))
    (comp (ref "T4") (value "M3铜柱螺丝孔") (footprint "螺丝孔-3mm") (libsource (lib "fszhang") (part "M3铜柱螺丝孔")))
    (comp (ref "T5")
      (value "QS30-1")
      (footprint "QS30-1")
      (description "南昌辉光管")
      (libsource (lib "fszhang") (part "QS30-1"))
    )
    (comp (ref "T6")
      (value "QS30-1")
      (footprint "QS30-1")
      (description "南昌辉光管")
      (libsource (lib "fszhang") (part "QS30-1"))
    )
    (comp (ref "T7")
      (value "QS30-1")
      (footprint "QS30-1")
      (description "南昌辉光管")
      (libsource (lib "fszhang") (part "QS30-1"))
    )
    (comp (ref "T8")
      (value "QS30-1")
      (footprint "QS30-1")
      (description "南昌辉光管")
      (libsource (lib "fszhang") (part "QS30-1"))
    )
    (comp (ref "U1")
      (value "MP1584 Module")
      (footprint "MP1584 Module")
      (libsource (lib "fszhang") (part "MP1584 Module"))
    )
    (comp (ref "U2")
      (value "WS2812-LED")
      (footprint "WS2812")
      (libsource (lib "fszhang") (part "WS2812-LED"))
    )
    (comp (ref "U3")
      (value "WS2812-LED")
      (footprint "WS2812")
      (libsource (lib "fszhang") (part "WS2812-LED"))
    )
    (comp (ref "U4")
      (value "WS2812-LED")
      (footprint "WS2812")
      (libsource (lib "fszhang") (part "WS2812-LED"))
    )
    (comp (ref "U5")
      (value "WS2812-LED")
      (footprint "WS2812")
      (libsource (lib "fszhang") (part "WS2812-LED"))
    )
    (comp (ref "U6")
      (value "MC34063A")
      (footprint "LC-SOIC-8_150mil")
      (libsource (lib "NIXIEClock_SCHLib") (part "MC34063A"))
    )
    (comp (ref "U7")
      (value "STM32F103RBT6")
      (footprint "LC-LQFP-64_10x10x05P")
      (description "ARM")
      (libsource (lib "Miscellaneous Devices LC") (part "STM32F103RBT6"))
    )
    (comp (ref "U8")
      (value "CH340G")
      (footprint "LC-SOIC-16_150mil")
      (description "USB")
      (libsource (lib "Miscellaneous Devices LC") (part "CH340G"))
    )
    (comp (ref "U9")
      (value "TM1812")
      (footprint "LC-SOIC-16_150mil")
      (libsource (lib "fszhang") (part "TM1812"))
    )
    (comp (ref "U10")
      (value "TM1812")
      (footprint "LC-SOIC-16_150mil")
      (libsource (lib "fszhang") (part "TM1812"))
    )
    (comp (ref "U11")
      (value "TM1812")
      (footprint "LC-SOIC-16_150mil")
      (libsource (lib "fszhang") (part "TM1812"))
    )
    (comp (ref "U12")
      (value "TM1812")
      (footprint "LC-SOIC-16_150mil")
      (libsource (lib "fszhang") (part "TM1812"))
    )
    (comp (ref "U13")
      (value "DS18B20")
      (footprint "TO-92A")
      (description "温度传感器")
      (libsource (lib "fszhang") (part "DS18B20"))
    )
    (comp (ref "U14")
      (value "DS3231M+TRL")
      (footprint "LC-SOIC-16_300mil")
      (description "实时时钟")
      (libsource (lib "Miscellaneous Devices LC") (part "DS3231M+TRL"))
    )
    (comp (ref "U15")
      (value "HX1838")
      (footprint "HS0038B")
      (description "红外接收器")
      (libsource (lib "fszhang") (part "HS0038B"))
    )
    (comp (ref "UP1")
      (value "Neon")
      (footprint "Neon")
      (description "氖泡")
      (libsource (lib "fszhang") (part "Neon"))
    )
    (comp (ref "UP2")
      (value "Neon")
      (footprint "Neon")
      (description "氖泡")
      (libsource (lib "fszhang") (part "Neon"))
    )
    (comp (ref "VR1")
      (value "AMS1117-3.3")
      (footprint "LC-SOT-223")
      (description "低压差线性稳压(LDO)")
      (libsource (lib "Miscellaneous Devices LC") (part "SOT-223 AMS1117-3.3"))
    )
    (comp (ref "Y1")
      (value "8M")
      (footprint "X-HC49U")
      (description "晶振")
      (fields (field (name "ALTIUM_VALUE") "8M") (field (name "PUBLISHER") "Altium Limited"))
      (libsource (lib "fszhang") (part "XTAL"))
    )
    (comp (ref "Y2")
      (value "12M")
      (footprint "X-HC49U")
      (description "晶振")
      (fields (field (name "PUBLISHER") "Altium Limited"))
      (libsource (lib "fszhang") (part "XTAL"))
    )
  )
  (nets
    (net (code "1") (name "+5") (class "Default")
      (node (ref "C1") (pin "2") (pinfunction "2_2") (pintype "passive"))
      (node (ref "C19") (pin "1") (pinfunction "1_1") (pintype "passive"))
      (node (ref "C20") (pin "1") (pinfunction "1_1") (pintype "passive"))
      (node (ref "C21") (pin "1") (pinfunction "1_1") (pintype "passive"))
      (node (ref "C22") (pin "1") (pinfunction "1_1") (pintype "passive"))
      (node (ref "C4") (pin "1") (pinfunction "1_1") (pintype "passive"))
      (node (ref "C5") (pin "1") (pinfunction "1_1") (pintype "passive"))
      (node (ref "C6") (pin "1") (pinfunction "1_1") (pintype "passive"))
      (node (ref "C7") (pin "1") (pinfunction "1_1") (pintype "passive"))
      (node (ref "D1") (pin "1") (pinfunction "A_1") (pintype "passive"))
      (node (ref "J4") (pin "1") (pinfunction "1_1") (pintype "passive"))
      (node (ref "J7") (pin "1") (pinfunction "VCC_1") (pintype "passive"))
      (node (ref "J8") (pin "1") (pinfunction "0_1") (pintype "passive"))
      (node (ref "P2") (pin "4") (pinfunction "4_4") (pintype "passive"))
      (node (ref "U1") (pin "3") (pinfunction "OUT+_3") (pintype "passive"))
      (node (ref "U10") (pin "1") (pinfunction "VDD_1") (pintype "passive"))
      (node (ref "U11") (pin "1") (pinfunction "VDD_1") (pintype "passive"))
      (node (ref "U12") (pin "1") (pinfunction "VDD_1") (pintype "passive"))
      (node (ref "U2") (pin "1") (pinfunction "VDD_1") (pintype "passive"))
      (node (ref "U3") (pin "1") (pinfunction "VDD_1") (pintype "passive"))
      (node (ref "U4") (pin "1") (pinfunction "VDD_1") (pintype "passive"))
      (node (ref "U5") (pin "1") (pinfunction "VDD_1") (pintype "passive"))
      (node (ref "U9") (pin "1") (pinfunction "VDD_1") (pintype "passive"))
      (node (ref "VR1") (pin "3") (pinfunction "Vin_3") (pintype "passive"))
    )
    (net (code "2") (name "+12") (class "Default")
      (node (ref "J1") (pin "1") (pinfunction "1_1") (pintype "power_in"))
      (node (ref "J3") (pin "1") (pinfunction "1_1") (pintype "passive"))
      (node (ref "Q2") (pin "3") (pinfunction "C_3") (pintype "passive"))
      (node (ref "U1") (pin "2") (pinfunction "IN+_2") (pintype "passive"))
    )
    (net (code "3") (name "/BEEP") (class "Default")
      (node (ref "R70") (pin "1") (pinfunction "1_1") (pintype "passive"))
      (node (ref "U7") (pin "58") (pinfunction "PB6_58") (pintype "bidirectional"))
    )
    (net (code "4") (name "/BT0") (class "Default")
      (node (ref "R14") (pin "2") (pinfunction "2_2") (pintype "passive"))
      (node (ref "R61") (pin "1") (pinfunction "1_1") (pintype "passive"))
      (node (ref "U7") (pin "60") (pinfunction "BOOT0_60") (pintype "input"))
    )
    (net (code "5") (name "/BT1") (class "Default")
      (node (ref "R11") (pin "2") (pinfunction "2_2") (pintype "passive"))
      (node (ref "U7") (pin "28") (pinfunction "PB2_28") (pintype "bidirectional"))
    )
    (net (code "6") (name "/BoostONOFF") (class "Default")
      (node (ref "Q2") (pin "1") (pinfunction "B_1") (pintype "passive"))
      (node (ref "U7") (pin "20") (pinfunction "PA4_20") (pintype "bidirectional"))
    )
    (net (code "7") (name "/DIN1") (class "Default")
      (node (ref "U7") (pin "14") (pinfunction "PA0-WKUP_14") (pintype "bidirectional"))
      (node (ref "U9") (pin "16") (pinfunction "DIN_16") (pintype "passive"))
    )
    (net (code "8") (name "/DIN2") (class "Default")
      (node (ref "U10") (pin "16") (pinfunction "DIN_16") (pintype "passive"))
      (node (ref "U7") (pin "15") (pinfunction "PA1_15") (pintype "bidirectional"))
    )
    (net (code "9") (name "/DIN3") (class "Default")
      (node (ref "U11") (pin "16") (pinfunction "DIN_16") (pintype "passive"))
      (node (ref "U7") (pin "16") (pinfunction "PA2_16") (pintype "bidirectional"))
    )
    (net (code "10") (name "/DIN4") (class "Default")
      (node (ref "U12") (pin "16") (pinfunction "DIN_16") (pintype "passive"))
      (node (ref "U7") (pin "17") (pinfunction "PA3_17") (pintype "bidirectional"))
    )
    (net (code "11") (name "/DS18B20") (class "Default")
      (node (ref "R62") (pin "2") (pinfunction "2_2") (pintype "passive"))
      (node (ref "U13") (pin "2") (pinfunction "DQ_2") (pintype "passive"))
      (node (ref "U7") (pin "61") (pinfunction "PB8_61") (pintype "bidirectional"))
    )
    (net (code "12") (name "/Dot1") (class "Default")
      (node (ref "Q1") (pin "1") (pinfunction "B_1") (pintype "passive"))
      (node (ref "R32") (pin "1") (pinfunction "1_1") (pintype "passive"))
    )
    (net (code "13") (name "/Dot2") (class "Default")
      (node (ref "Q3") (pin "1") (pinfunction "B_1") (pintype "passive"))
      (node (ref "R37") (pin "1") (pinfunction "1_1") (pintype "passive"))
    )
    (net (code "14") (name "/HX1838") (class "Default")
      (node (ref "R71") (pin "1") (pinfunction "1_1") (pintype "passive"))
      (node (ref "U15") (pin "1") (pinfunction "OUT_1") (pintype "passive"))
      (node (ref "U7") (pin "59") (pinfunction "PB7_59") (pintype "bidirectional"))
    )
    (net (code "15") (name "/INT#{slash}SQW") (class "Default")
      (node (ref "R69") (pin "1") (pinfunction "1_1") (pintype "passive"))
      (node (ref "U14") (pin "3") (pinfunction "~{INT}/SQW_3") (pintype "passive"))
      (node (ref "U7") (pin "27") (pinfunction "PB1_27") (pintype "bidirectional"))
    )
    (net (code "16") (name "/KEY1") (class "Default")
      (node (ref "C27") (pin "2") (pinfunction "2_2") (pintype "passive"))
      (node (ref "R65") (pin "2") (pinfunction "2_2") (pintype "passive"))
      (node (ref "S2") (pin "2") (pinfunction "2_2") (pintype "passive"))
      (node (ref "U7") (pin "8") (pinfunction "PC0_8") (pintype "bidirectional"))
    )
    (net (code "17") (name "/KEY2") (class "Default")
      (node (ref "C28") (pin "2") (pinfunction "2_2") (pintype "passive"))
      (node (ref "R66") (pin "2") (pinfunction "2_2") (pintype "passive"))
      (node (ref "S3") (pin "2") (pinfunction "2_2") (pintype "passive"))
      (node (ref "U7") (pin "9") (pinfunction "PC1_9") (pintype "bidirectional"))
    )
    (net (code "18") (name "/KEY3") (class "Default")
      (node (ref "C29") (pin "2") (pinfunction "2_2") (pintype "passive"))
      (node (ref "R67") (pin "2") (pinfunction "2_2") (pintype "passive"))
      (node (ref "S4") (pin "2") (pinfunction "2_2") (pintype "passive"))
      (node (ref "U7") (pin "10") (pinfunction "PC2_10") (pintype "bidirectional"))
    )
    (net (code "19") (name "/KEY4") (class "Default")
      (node (ref "C30") (pin "2") (pinfunction "2_2") (pintype "passive"))
      (node (ref "R68") (pin "2") (pinfunction "2_2") (pintype "passive"))
      (node (ref "S5") (pin "2") (pinfunction "2_2") (pintype "passive"))
      (node (ref "U7") (pin "11") (pinfunction "PC3_11") (pintype "bidirectional"))
    )
    (net (code "20") (name "/LED_DEBUG") (class "Default")
      (node (ref "R10") (pin "2") (pinfunction "2_2") (pintype "passive"))
      (node (ref "U7") (pin "22") (pinfunction "PA6_22") (pintype "bidirectional"))
    )
    (net (code "21") (name "/Lamp") (class "Default")
      (node (ref "P1") (pin "1") (pinfunction "1_1") (pintype "passive"))
      (node (ref "U7") (pin "23") (pinfunction "PA7_23") (pintype "bidirectional"))
    )
    (net (code "22") (name "/MetalKey") (class "Default")
      (node (ref "C3") (pin "2") (pinfunction "2_2") (pintype "passive"))
      (node (ref "P1") (pin "4") (pinfunction "4_4") (pintype "passive"))
      (node (ref "R1") (pin "2") (pinfunction "2_2") (pintype "passive"))
      (node (ref "U7") (pin "36") (pinfunction "PB15_36") (pintype "bidirectional"))
    )
    (net (code "23") (name "/RGB") (class "Default")
      (node (ref "U2") (pin "4") (pinfunction "DI_4") (pintype "passive"))
      (node (ref "U7") (pin "26") (pinfunction "PB0_26") (pintype "bidirectional"))
    )
    (net (code "24") (name "/RST") (class "Default")
      (node (ref "C18") (pin "2") (pinfunction "2_2") (pintype "passive"))
      (node (ref "D4") (pin "1") (pinfunction "A_1") (pintype "passive"))
      (node (ref "R15") (pin "2") (pinfunction "2_2") (pintype "passive"))
      (node (ref "S1") (pin "1") (pinfunction "1_1") (pintype "passive"))
      (node (ref "U7") (pin "7") (pinfunction "NRST_7") (pintype "bidirectional"))
    )
    (net (code "25") (name "/RX1") (class "Default")
      (node (ref "P3") (pin "3") (pinfunction "3_3") (pintype "passive"))
      (node (ref "U7") (pin "43") (pinfunction "PA10_43") (pintype "bidirectional"))
      (node (ref "U8") (pin "2") (pinfunction "TXD_2") (pintype "passive"))
    )
    (net (code "26") (name "/SCL") (class "Default")
      (node (ref "R63") (pin "2") (pinfunction "2_2") (pintype "passive"))
      (node (ref "U14") (pin "16") (pinfunction "SCL_16") (pintype "passive"))
      (node (ref "U7") (pin "56") (pinfunction "PB4_56") (pintype "bidirectional"))
    )
    (net (code "27") (name "/SDA") (class "Default")
      (node (ref "R64") (pin "2") (pinfunction "2_2") (pintype "passive"))
      (node (ref "U14") (pin "15") (pinfunction "SDA_15") (pintype "passive"))
      (node (ref "U7") (pin "55") (pinfunction "PB3_55") (pintype "bidirectional"))
    )
    (net (code "28") (name "/SWCLK") (class "Default")
      (node (ref "P2") (pin "2") (pinfunction "2_2") (pintype "passive"))
      (node (ref "U7") (pin "49") (pinfunction "PA14_49") (pintype "bidirectional"))
    )
    (net (code "29") (name "/SWDIO") (class "Default")
      (node (ref "P2") (pin "3") (pinfunction "3_3") (pintype "passive"))
      (node (ref "U7") (pin "46") (pinfunction "PA13_46") (pintype "bidirectional"))
    )
    (net (code "30") (name "/TX1") (class "Default")
      (node (ref "P3") (pin "2") (pinfunction "2_2") (pintype "passive"))
      (node (ref "U7") (pin "42") (pinfunction "PA9_42") (pintype "bidirectional"))
      (node (ref "U8") (pin "3") (pinfunction "RXD_3") (pintype "passive"))
    )
    (net (code "31") (name "/Tube1-0") (class "Default")
      (node (ref "Q5") (pin "1") (pinfunction "B_1") (pintype "passive"))
      (node (ref "R18") (pin "2") (pinfunction "2_2") (pintype "passive"))
    )
    (net (code "32") (name "/Tube1-1") (class "Default")
      (node (ref "Q14") (pin "1") (pinfunction "B_1") (pintype "passive"))
      (node (ref "R23") (pin "2") (pinfunction "2_2") (pintype "passive"))
    )
    (net (code "33") (name "/Tube1-2") (class "Default")
      (node (ref "Q13") (pin "1") (pinfunction "B_1") (pintype "passive"))
      (node (ref "R31") (pin "2") (pinfunction "2_2") (pintype "passive"))
    )
    (net (code "34") (name "/Tube1-3") (class "Default")
      (node (ref "Q12") (pin "1") (pinfunction "B_1") (pintype "passive"))
      (node (ref "R36") (pin "2") (pinfunction "2_2") (pintype "passive"))
    )
    (net (code "35") (name "/Tube1-4") (class "Default")
      (node (ref "Q11") (pin "1") (pinfunction "B_1") (pintype "passive"))
      (node (ref "R42") (pin "2") (pinfunction "2_2") (pintype "passive"))
    )
    (net (code "36") (name "/Tube1-5") (class "Default")
      (node (ref "Q10") (pin "1") (pinfunction "B_1") (pintype "passive"))
      (node (ref "R50") (pin "2") (pinfunction "2_2") (pintype "passive"))
    )
    (net (code "37") (name "/Tube1-6") (class "Default")
      (node (ref "Q9") (pin "1") (pinfunction "B_1") (pintype "passive"))
      (node (ref "R41") (pin "1") (pinfunction "1_1") (pintype "passive"))
    )
    (net (code "38") (name "/Tube1-7") (class "Default")
      (node (ref "Q8") (pin "1") (pinfunction "B_1") (pintype "passive"))
      (node (ref "R49") (pin "1") (pinfunction "1_1") (pintype "passive"))
    )
    (net (code "39") (name "/Tube1-8") (class "Default")
      (node (ref "Q7") (pin "1") (pinfunction "B_1") (pintype "passive"))
      (node (ref "R57") (pin "1") (pinfunction "1_1") (pintype "passive"))
    )
    (net (code "40") (name "/Tube1-9") (class "Default")
      (node (ref "Q6") (pin "1") (pinfunction "B_1") (pintype "passive"))
      (node (ref "R22") (pin "1") (pinfunction "1_1") (pintype "passive"))
    )
    (net (code "41") (name "/Tube2-0") (class "Default")
      (node (ref "Q15") (pin "1") (pinfunction "B_1") (pintype "passive"))
      (node (ref "R19") (pin "2") (pinfunction "2_2") (pintype "passive"))
    )
    (net (code "42") (name "/Tube2-1") (class "Default")
      (node (ref "Q24") (pin "1") (pinfunction "B_1") (pintype "passive"))
      (node (ref "R25") (pin "2") (pinfunction "2_2") (pintype "passive"))
    )
    (net (code "43") (name "/Tube2-2") (class "Default")
      (node (ref "Q23") (pin "1") (pinfunction "B_1") (pintype "passive"))
      (node (ref "R33") (pin "2") (pinfunction "2_2") (pintype "passive"))
    )
    (net (code "44") (name "/Tube2-3") (class "Default")
      (node (ref "Q22") (pin "1") (pinfunction "B_1") (pintype "passive"))
      (node (ref "R38") (pin "2") (pinfunction "2_2") (pintype "passive"))
    )
    (net (code "45") (name "/Tube2-4") (class "Default")
      (node (ref "Q21") (pin "1") (pinfunction "B_1") (pintype "passive"))
      (node (ref "R44") (pin "2") (pinfunction "2_2") (pintype "passive"))
    )
    (net (code "46") (name "/Tube2-5") (class "Default")
      (node (ref "Q20") (pin "1") (pinfunction "B_1") (pintype "passive"))
      (node (ref "R52") (pin "2") (pinfunction "2_2") (pintype "passive"))
    )
    (net (code "47") (name "/Tube2-6") (class "Default")
      (node (ref "Q19") (pin "1") (pinfunction "B_1") (pintype "passive"))
      (node (ref "R43") (pin "1") (pinfunction "1_1") (pintype "passive"))
    )
    (net (code "48") (name "/Tube2-7") (class "Default")
      (node (ref "Q18") (pin "1") (pinfunction "B_1") (pintype "passive"))
      (node (ref "R51") (pin "1") (pinfunction "1_1") (pintype "passive"))
    )
    (net (code "49") (name "/Tube2-8") (class "Default")
      (node (ref "Q17") (pin "1") (pinfunction "B_1") (pintype "passive"))
      (node (ref "R58") (pin "1") (pinfunction "1_1") (pintype "passive"))
    )
    (net (code "50") (name "/Tube2-9") (class "Default")
      (node (ref "Q16") (pin "1") (pinfunction "B_1") (pintype "passive"))
      (node (ref "R24") (pin "1") (pinfunction "1_1") (pintype "passive"))
    )
    (net (code "51") (name "/Tube3-0") (class "Default")
      (node (ref "Q25") (pin "1") (pinfunction "B_1") (pintype "passive"))
      (node (ref "R20") (pin "2") (pinfunction "2_2") (pintype "passive"))
    )
    (net (code "52") (name "/Tube3-1") (class "Default")
      (node (ref "Q34") (pin "1") (pinfunction "B_1") (pintype "passive"))
      (node (ref "R27") (pin "2") (pinfunction "2_2") (pintype "passive"))
    )
    (net (code "53") (name "/Tube3-2") (class "Default")
      (node (ref "Q33") (pin "1") (pinfunction "B_1") (pintype "passive"))
      (node (ref "R34") (pin "2") (pinfunction "2_2") (pintype "passive"))
    )
    (net (code "54") (name "/Tube3-3") (class "Default")
      (node (ref "Q32") (pin "1") (pinfunction "B_1") (pintype "passive"))
      (node (ref "R39") (pin "2") (pinfunction "2_2") (pintype "passive"))
    )
    (net (code "55") (name "/Tube3-4") (class "Default")
      (node (ref "Q31") (pin "1") (pinfunction "B_1") (pintype "passive"))
      (node (ref "R46") (pin "2") (pinfunction "2_2") (pintype "passive"))
    )
    (net (code "56") (name "/Tube3-5") (class "Default")
      (node (ref "Q30") (pin "1") (pinfunction "B_1") (pintype "passive"))
      (node (ref "R54") (pin "2") (pinfunction "2_2") (pintype "passive"))
    )
    (net (code "57") (name "/Tube3-6") (class "Default")
      (node (ref "Q29") (pin "1") (pinfunction "B_1") (pintype "passive"))
      (node (ref "R45") (pin "1") (pinfunction "1_1") (pintype "passive"))
    )
    (net (code "58") (name "/Tube3-7") (class "Default")
      (node (ref "Q28") (pin "1") (pinfunction "B_1") (pintype "passive"))
      (node (ref "R53") (pin "1") (pinfunction "1_1") (pintype "passive"))
    )
    (net (code "59") (name "/Tube3-8") (class "Default")
      (node (ref "Q27") (pin "1") (pinfunction "B_1") (pintype "passive"))
      (node (ref "R59") (pin "1") (pinfunction "1_1") (pintype "passive"))
    )
    (net (code "60") (name "/Tube3-9") (class "Default")
      (node (ref "Q26") (pin "1") (pinfunction "B_1") (pintype "passive"))
      (node (ref "R26") (pin "1") (pinfunction "1_1") (pintype "passive"))
    )
    (net (code "61") (name "/Tube4-0") (class "Default")
      (node (ref "Q35") (pin "1") (pinfunction "B_1") (pintype "passive"))
      (node (ref "R21") (pin "2") (pinfunction "2_2") (pintype "passive"))
    )
    (net (code "62") (name "/Tube4-1") (class "Default")
      (node (ref "Q44") (pin "1") (pinfunction "B_1") (pintype "passive"))
      (node (ref "R29") (pin "2") (pinfunction "2_2") (pintype "passive"))
    )
    (net (code "63") (name "/Tube4-2") (class "Default")
      (node (ref "Q43") (pin "1") (pinfunction "B_1") (pintype "passive"))
      (node (ref "R35") (pin "2") (pinfunction "2_2") (pintype "passive"))
    )
    (net (code "64") (name "/Tube4-3") (class "Default")
      (node (ref "Q42") (pin "1") (pinfunction "B_1") (pintype "passive"))
      (node (ref "R40") (pin "2") (pinfunction "2_2") (pintype "passive"))
    )
    (net (code "65") (name "/Tube4-4") (class "Default")
      (node (ref "Q41") (pin "1") (pinfunction "B_1") (pintype "passive"))
      (node (ref "R48") (pin "2") (pinfunction "2_2") (pintype "passive"))
    )
    (net (code "66") (name "/Tube4-5") (class "Default")
      (node (ref "Q40") (pin "1") (pinfunction "B_1") (pintype "passive"))
      (node (ref "R56") (pin "2") (pinfunction "2_2") (pintype "passive"))
    )
    (net (code "67") (name "/Tube4-6") (class "Default")
      (node (ref "Q39") (pin "1") (pinfunction "B_1") (pintype "passive"))
      (node (ref "R47") (pin "1") (pinfunction "1_1") (pintype "passive"))
    )
    (net (code "68") (name "/Tube4-7") (class "Default")
      (node (ref "Q38") (pin "1") (pinfunction "B_1") (pintype "passive"))
      (node (ref "R55") (pin "1") (pinfunction "1_1") (pintype "passive"))
    )
    (net (code "69") (name "/Tube4-8") (class "Default")
      (node (ref "Q37") (pin "1") (pinfunction "B_1") (pintype "passive"))
      (node (ref "R60") (pin "1") (pinfunction "1_1") (pintype "passive"))
    )
    (net (code "70") (name "/Tube4-9") (class "Default")
      (node (ref "Q36") (pin "1") (pinfunction "B_1") (pintype "passive"))
      (node (ref "R28") (pin "1") (pinfunction "1_1") (pintype "passive"))
    )
    (net (code "71") (name "/UD+") (class "Default")
      (node (ref "J7") (pin "3") (pinfunction "D+_3") (pintype "passive"))
      (node (ref "U8") (pin "5") (pinfunction "UD+_5") (pintype "passive"))
    )
    (net (code "72") (name "/UD-") (class "Default")
      (node (ref "J7") (pin "2") (pinfunction "D-_2") (pintype "passive"))
      (node (ref "U8") (pin "6") (pinfunction "UD-_6") (pintype "passive"))
    )
    (net (code "73") (name "3V3") (class "Default")
      (node (ref "C15") (pin "1") (pinfunction "1_1") (pintype "passive"))
      (node (ref "C16") (pin "1") (pinfunction "1_1") (pintype "passive"))
      (node (ref "C17") (pin "1") (pinfunction "1_1") (pintype "passive"))
      (node (ref "C2") (pin "2") (pinfunction "2_2") (pintype "passive"))
      (node (ref "C26") (pin "2") (pinfunction "2_2") (pintype "passive"))
      (node (ref "C31") (pin "1") (pinfunction "1_1") (pintype "passive"))
      (node (ref "D3") (pin "A") (pinfunction "A_A") (pintype "passive"))
      (node (ref "J5") (pin "1") (pinfunction "1_1") (pintype "passive"))
      (node (ref "P1") (pin "2") (pinfunction "2_2") (pintype "passive"))
      (node (ref "Q46") (pin "2") (pinfunction "E_2") (pintype "passive"))
      (node (ref "R1") (pin "1") (pinfunction "1_1") (pintype "passive"))
      (node (ref "R15") (pin "1") (pinfunction "1_1") (pintype "passive"))
      (node (ref "R16") (pin "2") (pinfunction "2_2") (pintype "passive"))
      (node (ref "R62") (pin "1") (pinfunction "1_1") (pintype "passive"))
      (node (ref "R63") (pin "1") (pinfunction "1_1") (pintype "passive"))
      (node (ref "R64") (pin "1") (pinfunction "1_1") (pintype "passive"))
      (node (ref "R65") (pin "1") (pinfunction "1_1") (pintype "passive"))
      (node (ref "R66") (pin "1") (pinfunction "1_1") (pintype "passive"))
      (node (ref "R67") (pin "1") (pinfunction "1_1") (pintype "passive"))
      (node (ref "R68") (pin "1") (pinfunction "1_1") (pintype "passive"))
      (node (ref "R69") (pin "2") (pinfunction "2_2") (pintype "passive"))
      (node (ref "R71") (pin "2") (pinfunction "2_2") (pintype "passive"))
      (node (ref "U13") (pin "3") (pinfunction "VDD_3") (pintype "passive"))
      (node (ref "U14") (pin "2") (pinfunction "VCC_2") (pintype "passive"))
      (node (ref "U15") (pin "3") (pinfunction "VCC_3") (pintype "passive"))
      (node (ref "U7") (pin "1") (pinfunction "VBAT_1") (pintype "power_in"))
      (node (ref "U7") (pin "13") (pinfunction "VDDA_13") (pintype "power_in"))
      (node (ref "U7") (pin "19") (pinfunction "VDD_4_19") (pintype "power_in"))
      (node (ref "U7") (pin "32") (pinfunction "VDD_1_32") (pintype "power_in"))
      (node (ref "U7") (pin "48") (pinfunction "VDD_2_48") (pintype "power_in"))
      (node (ref "U7") (pin "64") (pinfunction "VDD_3_64") (pintype "power_in"))
      (node (ref "U8") (pin "16") (pinfunction "VCC_16") (pintype "passive"))
      (node (ref "VR1") (pin "2") (pinfunction "Vout_2") (pintype "passive"))
    )
    (net (code "74") (name "DGND") (class "Default")
      (node (ref "BT1") (pin "2") (pinfunction "-_2") (pintype "passive"))
      (node (ref "C13") (pin "1") (pinfunction "1_1") (pintype "passive"))
      (node (ref "C14") (pin "1") (pinfunction "1_1") (pintype "passive"))
      (node (ref "C15") (pin "2") (pinfunction "2_2") (pintype "passive"))
      (node (ref "C16") (pin "2") (pinfunction "2_2") (pintype "passive"))
      (node (ref "C17") (pin "2") (pinfunction "2_2") (pintype "passive"))
      (node (ref "C18") (pin "1") (pinfunction "1_1") (pintype "passive"))
      (node (ref "C19") (pin "2") (pinfunction "2_2") (pintype "passive"))
      (node (ref "C20") (pin "2") (pinfunction "2_2") (pintype "passive"))
      (node (ref "C21") (pin "2") (pinfunction "2_2") (pintype "passive"))
      (node (ref "C22") (pin "2") (pinfunction "2_2") (pintype "passive"))
      (node (ref "C23") (pin "2") (pinfunction "2_2") (pintype "passive"))
      (node (ref "C24") (pin "2") (pinfunction "2_2") (pintype "passive"))
      (node (ref "C25") (pin "2") (pinfunction "2_2") (pintype "passive"))
      (node (ref "C26") (pin "1") (pinfunction "1_1") (pintype "passive"))
      (node (ref "C27") (pin "1") (pinfunction "1_1") (pintype "passive"))
      (node (ref "C28") (pin "1") (pinfunction "1_1") (pintype "passive"))
      (node (ref "C29") (pin "1") (pinfunction "1_1") (pintype "passive"))
      (node (ref "C3") (pin "1") (pinfunction "1_1") (pintype "passive"))
      (node (ref "C30") (pin "1") (pinfunction "1_1") (pintype "passive"))
      (node (ref "C31") (pin "2") (pinfunction "2_2") (pintype "passive"))
      (node (ref "J7") (pin "4") (pinfunction "ID_4") (pintype "passive"))
      (node (ref "J7") (pin "5") (pinfunction "VSS_5") (pintype "passive"))
      (node (ref "L2") (pin "2") (pinfunction "2_2") (pintype "passive"))
      (node (ref "P1") (pin "3") (pinfunction "3_3") (pintype "passive"))
      (node (ref "P2") (pin "1") (pinfunction "1_1") (pintype "passive"))
      (node (ref "P3") (pin "1") (pinfunction "1_1") (pintype "passive"))
      (node (ref "Q47") (pin "2") (pinfunction "E_2") (pintype "passive"))
      (node (ref "R11") (pin "1") (pinfunction "1_1") (pintype "passive"))
      (node (ref "R14") (pin "1") (pinfunction "1_1") (pintype "passive"))
      (node (ref "S1") (pin "2") (pinfunction "2_2") (pintype "passive"))
      (node (ref "S2") (pin "1") (pinfunction "1_1") (pintype "passive"))
      (node (ref "S3") (pin "1") (pinfunction "1_1") (pintype "passive"))
      (node (ref "S4") (pin "1") (pinfunction "1_1") (pintype "passive"))
      (node (ref "S5") (pin "1") (pinfunction "1_1") (pintype "passive"))
      (node (ref "U10") (pin "9") (pinfunction "GND_9") (pintype "passive"))
      (node (ref "U11") (pin "9") (pinfunction "GND_9") (pintype "passive"))
      (node (ref "U12") (pin "9") (pinfunction "GND_9") (pintype "passive"))
      (node (ref "U13") (pin "1") (pinfunction "GND_1") (pintype "passive"))
      (node (ref "U14") (pin "10") (pinfunction "N.C._10") (pintype "passive"))
      (node (ref "U14") (pin "11") (pinfunction "N.C._11") (pintype "passive"))
      (node (ref "U14") (pin "12") (pinfunction "N.C._12") (pintype "passive"))
      (node (ref "U14") (pin "13") (pinfunction "GND_13") (pintype "passive"))
      (node (ref "U14") (pin "5") (pinfunction "N.C._5") (pintype "passive"))
      (node (ref "U14") (pin "6") (pinfunction "N.C._6") (pintype "passive"))
      (node (ref "U14") (pin "7") (pinfunction "N.C._7") (pintype "passive"))
      (node (ref "U14") (pin "8") (pinfunction "N.C._8") (pintype "passive"))
      (node (ref "U14") (pin "9") (pinfunction "N.C._9") (pintype "passive"))
      (node (ref "U15") (pin "2") (pinfunction "GND_2") (pintype "passive"))
      (node (ref "U7") (pin "12") (pinfunction "VSSA_12") (pintype "power_in"))
      (node (ref "U7") (pin "18") (pinfunction "VSS_4_18") (pintype "power_in"))
      (node (ref "U7") (pin "31") (pinfunction "VSS_1_31") (pintype "power_in"))
      (node (ref "U7") (pin "47") (pinfunction "VSS_2_47") (pintype "power_in"))
      (node (ref "U7") (pin "63") (pinfunction "VSS_3_63") (pintype "power_in"))
      (node (ref "U8") (pin "1") (pinfunction "GND_1") (pintype "passive"))
      (node (ref "U9") (pin "9") (pinfunction "GND_9") (pintype "passive"))
    )
    (net (code "75") (name "GND") (class "Default")
      (node (ref "C1") (pin "1") (pinfunction "1_1") (pintype "passive"))
      (node (ref "C10") (pin "2") (pinfunction "2_2") (pintype "passive"))
      (node (ref "C11") (pin "1") (pinfunction "1_1") (pintype "passive"))
      (node (ref "C12") (pin "2") (pinfunction "2_2") (pintype "passive"))
      (node (ref "C2") (pin "1") (pinfunction "1_1") (pintype "passive"))
      (node (ref "C4") (pin "2") (pinfunction "2_2") (pintype "passive"))
      (node (ref "C5") (pin "2") (pinfunction "2_2") (pintype "passive"))
      (node (ref "C6") (pin "2") (pinfunction "2_2") (pintype "passive"))
      (node (ref "C7") (pin "2") (pinfunction "2_2") (pintype "passive"))
      (node (ref "C8") (pin "1") (pinfunction "1_1") (pintype "passive"))
      (node (ref "C9") (pin "2") (pinfunction "2_2") (pintype "passive"))
      (node (ref "D1") (pin "2") (pinfunction "K_2") (pintype "passive"))
      (node (ref "J6") (pin "1") (pinfunction "1_1") (pintype "passive"))
      (node (ref "L2") (pin "1") (pinfunction "1_1") (pintype "passive"))
      (node (ref "Q1") (pin "2") (pinfunction "E_2") (pintype "passive"))
      (node (ref "Q10") (pin "2") (pinfunction "E_2") (pintype "passive"))
      (node (ref "Q11") (pin "2") (pinfunction "E_2") (pintype "passive"))
      (node (ref "Q12") (pin "2") (pinfunction "E_2") (pintype "passive"))
      (node (ref "Q13") (pin "2") (pinfunction "E_2") (pintype "passive"))
      (node (ref "Q14") (pin "2") (pinfunction "E_2") (pintype "passive"))
      (node (ref "Q15") (pin "2") (pinfunction "E_2") (pintype "passive"))
      (node (ref "Q16") (pin "2") (pinfunction "E_2") (pintype "passive"))
      (node (ref "Q17") (pin "2") (pinfunction "E_2") (pintype "passive"))
      (node (ref "Q18") (pin "2") (pinfunction "E_2") (pintype "passive"))
      (node (ref "Q19") (pin "2") (pinfunction "E_2") (pintype "passive"))
      (node (ref "Q20") (pin "2") (pinfunction "E_2") (pintype "passive"))
      (node (ref "Q21") (pin "2") (pinfunction "E_2") (pintype "passive"))
      (node (ref "Q22") (pin "2") (pinfunction "E_2") (pintype "passive"))
      (node (ref "Q23") (pin "2") (pinfunction "E_2") (pintype "passive"))
      (node (ref "Q24") (pin "2") (pinfunction "E_2") (pintype "passive"))
      (node (ref "Q25") (pin "2") (pinfunction "E_2") (pintype "passive"))
      (node (ref "Q26") (pin "2") (pinfunction "E_2") (pintype "passive"))
      (node (ref "Q27") (pin "2") (pinfunction "E_2") (pintype "passive"))
      (node (ref "Q28") (pin "2") (pinfunction "E_2") (pintype "passive"))
      (node (ref "Q29") (pin "2") (pinfunction "E_2") (pintype "passive"))
      (node (ref "Q3") (pin "2") (pinfunction "E_2") (pintype "passive"))
      (node (ref "Q30") (pin "2") (pinfunction "E_2") (pintype "passive"))
      (node (ref "Q31") (pin "2") (pinfunction "E_2") (pintype "passive"))
      (node (ref "Q32") (pin "2") (pinfunction "E_2") (pintype "passive"))
      (node (ref "Q33") (pin "2") (pinfunction "E_2") (pintype "passive"))
      (node (ref "Q34") (pin "2") (pinfunction "E_2") (pintype "passive"))
      (node (ref "Q35") (pin "2") (pinfunction "E_2") (pintype "passive"))
      (node (ref "Q36") (pin "2") (pinfunction "E_2") (pintype "passive"))
      (node (ref "Q37") (pin "2") (pinfunction "E_2") (pintype "passive"))
      (node (ref "Q38") (pin "2") (pinfunction "E_2") (pintype "passive"))
      (node (ref "Q39") (pin "2") (pinfunction "E_2") (pintype "passive"))
      (node (ref "Q4") (pin "S") (pinfunction "S_S") (pintype "passive"))
      (node (ref "Q40") (pin "2") (pinfunction "E_2") (pintype "passive"))
      (node (ref "Q41") (pin "2") (pinfunction "E_2") (pintype "passive"))
      (node (ref "Q42") (pin "2") (pinfunction "E_2") (pintype "passive"))
      (node (ref "Q43") (pin "2") (pinfunction "E_2") (pintype "passive"))
      (node (ref "Q44") (pin "2") (pinfunction "E_2") (pintype "passive"))
      (node (ref "Q5") (pin "2") (pinfunction "E_2") (pintype "passive"))
      (node (ref "Q6") (pin "2") (pinfunction "E_2") (pintype "passive"))
      (node (ref "Q7") (pin "2") (pinfunction "E_2") (pintype "passive"))
      (node (ref "Q8") (pin "2") (pinfunction "E_2") (pintype "passive"))
      (node (ref "Q9") (pin "2") (pinfunction "E_2") (pintype "passive"))
      (node (ref "R2") (pin "1") (pinfunction "1_1") (pintype "passive"))
      (node (ref "R8") (pin "1") (pinfunction "1_1") (pintype "passive"))
      (node (ref "U1") (pin "4") (pinfunction "OUT-_4") (pintype "passive"))
      (node (ref "U2") (pin "3") (pinfunction "VSS_3") (pintype "passive"))
      (node (ref "U3") (pin "3") (pinfunction "VSS_3") (pintype "passive"))
      (node (ref "U4") (pin "3") (pinfunction "VSS_3") (pintype "passive"))
      (node (ref "U5") (pin "3") (pinfunction "VSS_3") (pintype "passive"))
      (node (ref "U6") (pin "4") (pinfunction "GND_4") (pintype "passive"))
      (node (ref "VR1") (pin "1") (pinfunction "GND_1") (pintype "passive"))
    )
    (net (code "76") (name "Net-(BT1-+)") (class "Default")
      (node (ref "BT1") (pin "1") (pinfunction "+_1") (pintype "passive"))
      (node (ref "U14") (pin "14") (pinfunction "VBAT_14") (pintype "passive"))
    )
    (net (code "77") (name "Net-(D2-A)") (class "Default")
      (node (ref "D2") (pin "1") (pinfunction "A_1") (pintype "passive"))
      (node (ref "L1") (pin "2") (pinfunction "2_2") (pintype "passive"))
      (node (ref "Q4") (pin "D") (pinfunction "D_D") (pintype "passive"))
    )
    (net (code "78") (name "Net-(D3-PadK)") (class "Default")
      (node (ref "D3") (pin "K") (pinfunction "K_K") (pintype "passive"))
      (node (ref "R10") (pin "1") (pinfunction "1_1") (pintype "passive"))
    )
    (net (code "79") (name "Net-(D4-K)") (class "Default")
      (node (ref "D4") (pin "2") (pinfunction "K_2") (pintype "passive"))
      (node (ref "Q45") (pin "3") (pinfunction "C_3") (pintype "passive"))
      (node (ref "R16") (pin "1") (pinfunction "1_1") (pintype "passive"))
    )
    (net (code "80") (name "Net-(J8-1)") (class "Default")
      (node (ref "J8") (pin "2") (pinfunction "1_2") (pintype "passive"))
      (node (ref "Q47") (pin "3") (pinfunction "C_3") (pintype "passive"))
    )
    (net (code "81") (name "Net-(Q1-C)") (class "Default")
      (node (ref "Q1") (pin "3") (pinfunction "C_3") (pintype "passive"))
      (node (ref "UP1") (pin "2") (pinfunction "2_2") (pintype "passive"))
    )
    (net (code "82") (name "Net-(Q2-E)") (class "Default")
      (node (ref "C11") (pin "2") (pinfunction "2_2") (pintype "passive"))
      (node (ref "C12") (pin "1") (pinfunction "1_1") (pintype "passive"))
      (node (ref "L1") (pin "1") (pinfunction "1_1") (pintype "passive"))
      (node (ref "Q2") (pin "2") (pinfunction "E_2") (pintype "passive"))
      (node (ref "U6") (pin "1") (pinfunction "SC_1") (pintype "passive"))
      (node (ref "U6") (pin "6") (pinfunction "VCC_6") (pintype "passive"))
      (node (ref "U6") (pin "7") (pinfunction "IPK_7") (pintype "passive"))
      (node (ref "U6") (pin "8") (pinfunction "DRI_8") (pintype "passive"))
    )
    (net (code "83") (name "Net-(Q3-C)") (class "Default")
      (node (ref "Q3") (pin "3") (pinfunction "C_3") (pintype "passive"))
      (node (ref "UP2") (pin "2") (pinfunction "2_2") (pintype "passive"))
    )
    (net (code "84") (name "Net-(Q5-C)") (class "Default")
      (node (ref "Q5") (pin "3") (pinfunction "C_3") (pintype "passive"))
      (node (ref "T5") (pin "3") (pinfunction "K'0'_3") (pintype "passive"))
    )
    (net (code "85") (name "Net-(Q6-C)") (class "Default")
      (node (ref "Q6") (pin "3") (pinfunction "C_3") (pintype "passive"))
      (node (ref "T5") (pin "4") (pinfunction "K'9'_4") (pintype "passive"))
    )
    (net (code "86") (name "Net-(Q7-C)") (class "Default")
      (node (ref "Q7") (pin "3") (pinfunction "C_3") (pintype "passive"))
      (node (ref "T5") (pin "5") (pinfunction "K'8'_5") (pintype "passive"))
    )
    (net (code "87") (name "Net-(Q8-C)") (class "Default")
      (node (ref "Q8") (pin "3") (pinfunction "C_3") (pintype "passive"))
      (node (ref "T5") (pin "6") (pinfunction "K'7'_6") (pintype "passive"))
    )
    (net (code "88") (name "Net-(Q9-C)") (class "Default")
      (node (ref "Q9") (pin "3") (pinfunction "C_3") (pintype "passive"))
      (node (ref "T5") (pin "7") (pinfunction "K'6'_7") (pintype "passive"))
    )
    (net (code "89") (name "Net-(Q10-C)") (class "Default")
      (node (ref "Q10") (pin "3") (pinfunction "C_3") (pintype "passive"))
      (node (ref "T5") (pin "9") (pinfunction "K'5'_9") (pintype "passive"))
    )
    (net (code "90") (name "Net-(Q11-C)") (class "Default")
      (node (ref "Q11") (pin "3") (pinfunction "C_3") (pintype "passive"))
      (node (ref "T5") (pin "10") (pinfunction "K'4'_10") (pintype "passive"))
    )
    (net (code "91") (name "Net-(Q12-C)") (class "Default")
      (node (ref "Q12") (pin "3") (pinfunction "C_3") (pintype "passive"))
      (node (ref "T5") (pin "11") (pinfunction "K'3'_11") (pintype "passive"))
    )
    (net (code "92") (name "Net-(Q13-C)") (class "Default")
      (node (ref "Q13") (pin "3") (pinfunction "C_3") (pintype "passive"))
      (node (ref "T5") (pin "12") (pinfunction "K'2'_12") (pintype "passive"))
    )
    (net (code "93") (name "Net-(Q14-C)") (class "Default")
      (node (ref "Q14") (pin "3") (pinfunction "C_3") (pintype "passive"))
      (node (ref "T5") (pin "13") (pinfunction "K'1'_13") (pintype "passive"))
    )
    (net (code "94") (name "Net-(Q15-C)") (class "Default")
      (node (ref "Q15") (pin "3") (pinfunction "C_3") (pintype "passive"))
      (node (ref "T6") (pin "3") (pinfunction "K'0'_3") (pintype "passive"))
    )
    (net (code "95") (name "Net-(Q16-C)") (class "Default")
      (node (ref "Q16") (pin "3") (pinfunction "C_3") (pintype "passive"))
      (node (ref "T6") (pin "4") (pinfunction "K'9'_4") (pintype "passive"))
    )
    (net (code "96") (name "Net-(Q17-C)") (class "Default")
      (node (ref "Q17") (pin "3") (pinfunction "C_3") (pintype "passive"))
      (node (ref "T6") (pin "5") (pinfunction "K'8'_5") (pintype "passive"))
    )
    (net (code "97") (name "Net-(Q18-C)") (class "Default")
      (node (ref "Q18") (pin "3") (pinfunction "C_3") (pintype "passive"))
      (node (ref "T6") (pin "6") (pinfunction "K'7'_6") (pintype "passive"))
    )
    (net (code "98") (name "Net-(Q19-C)") (class "Default")
      (node (ref "Q19") (pin "3") (pinfunction "C_3") (pintype "passive"))
      (node (ref "T6") (pin "7") (pinfunction "K'6'_7") (pintype "passive"))
    )
    (net (code "99") (name "Net-(Q20-C)") (class "Default")
      (node (ref "Q20") (pin "3") (pinfunction "C_3") (pintype "passive"))
      (node (ref "T6") (pin "9") (pinfunction "K'5'_9") (pintype "passive"))
    )
    (net (code "100") (name "Net-(Q21-C)") (class "Default")
      (node (ref "Q21") (pin "3") (pinfunction "C_3") (pintype "passive"))
      (node (ref "T6") (pin "10") (pinfunction "K'4'_10") (pintype "passive"))
    )
    (net (code "101") (name "Net-(Q22-C)") (class "Default")
      (node (ref "Q22") (pin "3") (pinfunction "C_3") (pintype "passive"))
      (node (ref "T6") (pin "11") (pinfunction "K'3'_11") (pintype "passive"))
    )
    (net (code "102") (name "Net-(Q23-C)") (class "Default")
      (node (ref "Q23") (pin "3") (pinfunction "C_3") (pintype "passive"))
      (node (ref "T6") (pin "12") (pinfunction "K'2'_12") (pintype "passive"))
    )
    (net (code "103") (name "Net-(Q24-C)") (class "Default")
      (node (ref "Q24") (pin "3") (pinfunction "C_3") (pintype "passive"))
      (node (ref "T6") (pin "13") (pinfunction "K'1'_13") (pintype "passive"))
    )
    (net (code "104") (name "Net-(Q25-C)") (class "Default")
      (node (ref "Q25") (pin "3") (pinfunction "C_3") (pintype "passive"))
      (node (ref "T7") (pin "3") (pinfunction "K'0'_3") (pintype "passive"))
    )
    (net (code "105") (name "Net-(Q26-C)") (class "Default")
      (node (ref "Q26") (pin "3") (pinfunction "C_3") (pintype "passive"))
      (node (ref "T7") (pin "4") (pinfunction "K'9'_4") (pintype "passive"))
    )
    (net (code "106") (name "Net-(Q27-C)") (class "Default")
      (node (ref "Q27") (pin "3") (pinfunction "C_3") (pintype "passive"))
      (node (ref "T7") (pin "5") (pinfunction "K'8'_5") (pintype "passive"))
    )
    (net (code "107") (name "Net-(Q28-C)") (class "Default")
      (node (ref "Q28") (pin "3") (pinfunction "C_3") (pintype "passive"))
      (node (ref "T7") (pin "6") (pinfunction "K'7'_6") (pintype "passive"))
    )
    (net (code "108") (name "Net-(Q29-C)") (class "Default")
      (node (ref "Q29") (pin "3") (pinfunction "C_3") (pintype "passive"))
      (node (ref "T7") (pin "7") (pinfunction "K'6'_7") (pintype "passive"))
    )
    (net (code "109") (name "Net-(Q30-C)") (class "Default")
      (node (ref "Q30") (pin "3") (pinfunction "C_3") (pintype "passive"))
      (node (ref "T7") (pin "9") (pinfunction "K'5'_9") (pintype "passive"))
    )
    (net (code "110") (name "Net-(Q31-C)") (class "Default")
      (node (ref "Q31") (pin "3") (pinfunction "C_3") (pintype "passive"))
      (node (ref "T7") (pin "10") (pinfunction "K'4'_10") (pintype "passive"))
    )
    (net (code "111") (name "Net-(Q32-C)") (class "Default")
      (node (ref "Q32") (pin "3") (pinfunction "C_3") (pintype "passive"))
      (node (ref "T7") (pin "11") (pinfunction "K'3'_11") (pintype "passive"))
    )
    (net (code "112") (name "Net-(Q33-C)") (class "Default")
      (node (ref "Q33") (pin "3") (pinfunction "C_3") (pintype "passive"))
      (node (ref "T7") (pin "12") (pinfunction "K'2'_12") (pintype "passive"))
    )
    (net (code "113") (name "Net-(Q34-C)") (class "Default")
      (node (ref "Q34") (pin "3") (pinfunction "C_3") (pintype "passive"))
      (node (ref "T7") (pin "13") (pinfunction "K'1'_13") (pintype "passive"))
    )
    (net (code "114") (name "Net-(Q35-C)") (class "Default")
      (node (ref "Q35") (pin "3") (pinfunction "C_3") (pintype "passive"))
      (node (ref "T8") (pin "3") (pinfunction "K'0'_3") (pintype "passive"))
    )
    (net (code "115") (name "Net-(Q36-C)") (class "Default")
      (node (ref "Q36") (pin "3") (pinfunction "C_3") (pintype "passive"))
      (node (ref "T8") (pin "4") (pinfunction "K'9'_4") (pintype "passive"))
    )
    (net (code "116") (name "Net-(Q37-C)") (class "Default")
      (node (ref "Q37") (pin "3") (pinfunction "C_3") (pintype "passive"))
      (node (ref "T8") (pin "5") (pinfunction "K'8'_5") (pintype "passive"))
    )
    (net (code "117") (name "Net-(Q38-C)") (class "Default")
      (node (ref "Q38") (pin "3") (pinfunction "C_3") (pintype "passive"))
      (node (ref "T8") (pin "6") (pinfunction "K'7'_6") (pintype "passive"))
    )
    (net (code "118") (name "Net-(Q39-C)") (class "Default")
      (node (ref "Q39") (pin "3") (pinfunction "C_3") (pintype "passive"))
      (node (ref "T8") (pin "7") (pinfunction "K'6'_7") (pintype "passive"))
    )
    (net (code "119") (name "Net-(Q40-C)") (class "Default")
      (node (ref "Q40") (pin "3") (pinfunction "C_3") (pintype "passive"))
      (node (ref "T8") (pin "9") (pinfunction "K'5'_9") (pintype "passive"))
    )
    (net (code "120") (name "Net-(Q41-C)") (class "Default")
      (node (ref "Q41") (pin "3") (pinfunction "C_3") (pintype "passive"))
      (node (ref "T8") (pin "10") (pinfunction "K'4'_10") (pintype "passive"))
    )
    (net (code "121") (name "Net-(Q42-C)") (class "Default")
      (node (ref "Q42") (pin "3") (pinfunction "C_3") (pintype "passive"))
      (node (ref "T8") (pin "11") (pinfunction "K'3'_11") (pintype "passive"))
    )
    (net (code "122") (name "Net-(Q43-C)") (class "Default")
      (node (ref "Q43") (pin "3") (pinfunction "C_3") (pintype "passive"))
      (node (ref "T8") (pin "12") (pinfunction "K'2'_12") (pintype "passive"))
    )
    (net (code "123") (name "Net-(Q44-C)") (class "Default")
      (node (ref "Q44") (pin "3") (pinfunction "C_3") (pintype "passive"))
      (node (ref "T8") (pin "13") (pinfunction "K'1'_13") (pintype "passive"))
    )
    (net (code "124") (name "Net-(Q45-B)") (class "Default")
      (node (ref "Q45") (pin "1") (pinfunction "B_1") (pintype "passive"))
      (node (ref "R17") (pin "2") (pinfunction "2_2") (pintype "passive"))
    )
    (net (code "125") (name "Net-(Q45-E)") (class "Default")
      (node (ref "Q45") (pin "2") (pinfunction "E_2") (pintype "passive"))
      (node (ref "R30") (pin "1") (pinfunction "1_1") (pintype "passive"))
      (node (ref "U8") (pin "11") (pinfunction "RTS#_11") (pintype "passive"))
    )
    (net (code "126") (name "Net-(Q46-B)") (class "Default")
      (node (ref "Q46") (pin "1") (pinfunction "B_1") (pintype "passive"))
      (node (ref "R30") (pin "2") (pinfunction "2_2") (pintype "passive"))
    )
    (net (code "127") (name "Net-(Q46-C)") (class "Default")
      (node (ref "Q46") (pin "3") (pinfunction "C_3") (pintype "passive"))
      (node (ref "R61") (pin "2") (pinfunction "2_2") (pintype "passive"))
    )
    (net (code "128") (name "Net-(Q47-B)") (class "Default")
      (node (ref "Q47") (pin "1") (pinfunction "B_1") (pintype "passive"))
      (node (ref "R70") (pin "2") (pinfunction "2_2") (pintype "passive"))
    )
    (net (code "129") (name "Net-(R4-Pad1)") (class "Default")
      (node (ref "R4") (pin "1") (pinfunction "1_1") (pintype "passive"))
      (node (ref "UP1") (pin "1") (pinfunction "1_1") (pintype "passive"))
    )
    (net (code "130") (name "Net-(R6-BOT)") (class "Default")
      (node (ref "R3") (pin "2") (pinfunction "2_2") (pintype "passive"))
      (node (ref "R6") (pin "3") (pinfunction "BOT_3") (pintype "passive"))
    )
    (net (code "131") (name "Net-(R9-Pad1)") (class "Default")
      (node (ref "R9") (pin "1") (pinfunction "1_1") (pintype "passive"))
      (node (ref "UP2") (pin "1") (pinfunction "1_1") (pintype "passive"))
    )
    (net (code "132") (name "Net-(T5-Anode)") (class "Default")
      (node (ref "R7") (pin "1") (pinfunction "1_1") (pintype "passive"))
      (node (ref "T5") (pin "2") (pinfunction "Anode_2") (pintype "passive"))
    )
    (net (code "133") (name "Net-(T6-Anode)") (class "Default")
      (node (ref "R5") (pin "1") (pinfunction "1_1") (pintype "passive"))
      (node (ref "T6") (pin "2") (pinfunction "Anode_2") (pintype "passive"))
    )
    (net (code "134") (name "Net-(T7-Anode)") (class "Default")
      (node (ref "R12") (pin "1") (pinfunction "1_1") (pintype "passive"))
      (node (ref "T7") (pin "2") (pinfunction "Anode_2") (pintype "passive"))
    )
    (net (code "135") (name "Net-(T8-Anode)") (class "Default")
      (node (ref "R13") (pin "1") (pinfunction "1_1") (pintype "passive"))
      (node (ref "T8") (pin "2") (pinfunction "Anode_2") (pintype "passive"))
    )
    (net (code "136") (name "Net-(U1-IN-)") (class "Default")
      (node (ref "J1") (pin "2") (pinfunction "2_2") (pintype "power_in"))
      (node (ref "J1") (pin "3") (pinfunction "3_3") (pintype "power_in"))
      (node (ref "U1") (pin "1") (pinfunction "IN-_1") (pintype "passive"))
    )
    (net (code "137") (name "Net-(U2-DO)") (class "Default")
      (node (ref "U2") (pin "2") (pinfunction "DO_2") (pintype "passive"))
      (node (ref "U3") (pin "4") (pinfunction "DI_4") (pintype "passive"))
    )
    (net (code "138") (name "Net-(U3-DO)") (class "Default")
      (node (ref "U3") (pin "2") (pinfunction "DO_2") (pintype "passive"))
      (node (ref "U4") (pin "4") (pinfunction "DI_4") (pintype "passive"))
    )
    (net (code "139") (name "Net-(U4-DO)") (class "Default")
      (node (ref "U4") (pin "2") (pinfunction "DO_2") (pintype "passive"))
      (node (ref "U5") (pin "4") (pinfunction "DI_4") (pintype "passive"))
    )
    (net (code "140") (name "Net-(U6-FB)") (class "Default")
      (node (ref "C8") (pin "2") (pinfunction "2_2") (pintype "passive"))
      (node (ref "R2") (pin "2") (pinfunction "2_2") (pintype "passive"))
      (node (ref "R3") (pin "1") (pinfunction "1_1") (pintype "passive"))
      (node (ref "U6") (pin "5") (pinfunction "FB_5") (pintype "passive"))
    )
    (net (code "141") (name "Net-(U6-SE)") (class "Default")
      (node (ref "Q4") (pin "G") (pinfunction "G_G") (pintype "passive"))
      (node (ref "R8") (pin "2") (pinfunction "2_2") (pintype "passive"))
      (node (ref "U6") (pin "2") (pinfunction "SE_2") (pintype "passive"))
    )
    (net (code "142") (name "Net-(U6-TC)") (class "Default")
      (node (ref "C9") (pin "1") (pinfunction "1_1") (pintype "passive"))
      (node (ref "U6") (pin "3") (pinfunction "TC_3") (pintype "passive"))
    )
    (net (code "143") (name "Net-(U7A-PD0-OSC_IN)") (class "Default")
      (node (ref "C13") (pin "2") (pinfunction "2_2") (pintype "passive"))
      (node (ref "U7") (pin "5") (pinfunction "PD0-OSC_IN_5") (pintype "bidirectional"))
      (node (ref "Y1") (pin "1") (pinfunction "OSC1_1") (pintype "passive"))
    )
    (net (code "144") (name "Net-(U7A-PD1)") (class "Default")
      (node (ref "C14") (pin "2") (pinfunction "2_2") (pintype "passive"))
      (node (ref "U7") (pin "6") (pinfunction "PD1_6") (pintype "bidirectional"))
      (node (ref "Y1") (pin "2") (pinfunction "OSC2_2") (pintype "passive"))
    )
    (net (code "145") (name "Net-(U8-DTR#)") (class "Default")
      (node (ref "R17") (pin "1") (pinfunction "1_1") (pintype "passive"))
      (node (ref "U8") (pin "12") (pinfunction "DTR#_12") (pintype "passive"))
    )
    (net (code "146") (name "Net-(U8-V3.3)") (class "Default")
      (node (ref "C23") (pin "1") (pinfunction "1_1") (pintype "passive"))
      (node (ref "U8") (pin "4") (pinfunction "V3.3_4") (pintype "passive"))
    )
    (net (code "147") (name "Net-(U8-XI)") (class "Default")
      (node (ref "C24") (pin "1") (pinfunction "1_1") (pintype "passive"))
      (node (ref "U8") (pin "7") (pinfunction "XI_7") (pintype "passive"))
      (node (ref "Y2") (pin "1") (pinfunction "OSC1_1") (pintype "passive"))
    )
    (net (code "148") (name "Net-(U8-XO)") (class "Default")
      (node (ref "C25") (pin "1") (pinfunction "1_1") (pintype "passive"))
      (node (ref "U8") (pin "8") (pinfunction "XO_8") (pintype "passive"))
      (node (ref "Y2") (pin "2") (pinfunction "OSC2_2") (pintype "passive"))
    )
    (net (code "149") (name "Net-(U9-1OUTB)") (class "Default")
      (node (ref "R31") (pin "1") (pinfunction "1_1") (pintype "passive"))
      (node (ref "U9") (pin "13") (pinfunction "1OUTB_13") (pintype "passive"))
    )
    (net (code "150") (name "Net-(U9-1OUTG)") (class "Default")
      (node (ref "R23") (pin "1") (pinfunction "1_1") (pintype "passive"))
      (node (ref "U9") (pin "14") (pinfunction "1OUTG_14") (pintype "passive"))
    )
    (net (code "151") (name "Net-(U9-1OUTR)") (class "Default")
      (node (ref "R18") (pin "1") (pinfunction "1_1") (pintype "passive"))
      (node (ref "U9") (pin "15") (pinfunction "1OUTR_15") (pintype "passive"))
    )
    (net (code "152") (name "Net-(U9-2OUTB)") (class "Default")
      (node (ref "R50") (pin "1") (pinfunction "1_1") (pintype "passive"))
      (node (ref "U9") (pin "10") (pinfunction "2OUTB_10") (pintype "passive"))
    )
    (net (code "153") (name "Net-(U9-2OUTG)") (class "Default")
      (node (ref "R42") (pin "1") (pinfunction "1_1") (pintype "passive"))
      (node (ref "U9") (pin "11") (pinfunction "2OUTG_11") (pintype "passive"))
    )
    (net (code "154") (name "Net-(U9-2OUTR)") (class "Default")
      (node (ref "R36") (pin "1") (pinfunction "1_1") (pintype "passive"))
      (node (ref "U9") (pin "12") (pinfunction "2OUTR_12") (pintype "passive"))
    )
    (net (code "155") (name "Net-(U9-3OUTB)") (class "Default")
      (node (ref "R57") (pin "2") (pinfunction "2_2") (pintype "passive"))
      (node (ref "U9") (pin "8") (pinfunction "3OUTB_8") (pintype "passive"))
    )
    (net (code "156") (name "Net-(U9-3OUTG)") (class "Default")
      (node (ref "R49") (pin "2") (pinfunction "2_2") (pintype "passive"))
      (node (ref "U9") (pin "7") (pinfunction "3OUTG_7") (pintype "passive"))
    )
    (net (code "157") (name "Net-(U9-3OUTR)") (class "Default")
      (node (ref "R41") (pin "2") (pinfunction "2_2") (pintype "passive"))
      (node (ref "U9") (pin "6") (pinfunction "3OUTR_6") (pintype "passive"))
    )
    (net (code "158") (name "Net-(U9-4OUTR)") (class "Default")
      (node (ref "R22") (pin "2") (pinfunction "2_2") (pintype "passive"))
      (node (ref "U9") (pin "3") (pinfunction "4OUTR_3") (pintype "passive"))
    )
    (net (code "159") (name "Net-(U10-1OUTB)") (class "Default")
      (node (ref "R33") (pin "1") (pinfunction "1_1") (pintype "passive"))
      (node (ref "U10") (pin "13") (pinfunction "1OUTB_13") (pintype "passive"))
    )
    (net (code "160") (name "Net-(U10-1OUTG)") (class "Default")
      (node (ref "R25") (pin "1") (pinfunction "1_1") (pintype "passive"))
      (node (ref "U10") (pin "14") (pinfunction "1OUTG_14") (pintype "passive"))
    )
    (net (code "161") (name "Net-(U10-1OUTR)") (class "Default")
      (node (ref "R19") (pin "1") (pinfunction "1_1") (pintype "passive"))
      (node (ref "U10") (pin "15") (pinfunction "1OUTR_15") (pintype "passive"))
    )
    (net (code "162") (name "Net-(U10-2OUTB)") (class "Default")
      (node (ref "R52") (pin "1") (pinfunction "1_1") (pintype "passive"))
      (node (ref "U10") (pin "10") (pinfunction "2OUTB_10") (pintype "passive"))
    )
    (net (code "163") (name "Net-(U10-2OUTG)") (class "Default")
      (node (ref "R44") (pin "1") (pinfunction "1_1") (pintype "passive"))
      (node (ref "U10") (pin "11") (pinfunction "2OUTG_11") (pintype "passive"))
    )
    (net (code "164") (name "Net-(U10-2OUTR)") (class "Default")
      (node (ref "R38") (pin "1") (pinfunction "1_1") (pintype "passive"))
      (node (ref "U10") (pin "12") (pinfunction "2OUTR_12") (pintype "passive"))
    )
    (net (code "165") (name "Net-(U10-3OUTB)") (class "Default")
      (node (ref "R58") (pin "2") (pinfunction "2_2") (pintype "passive"))
      (node (ref "U10") (pin "8") (pinfunction "3OUTB_8") (pintype "passive"))
    )
    (net (code "166") (name "Net-(U10-3OUTG)") (class "Default")
      (node (ref "R51") (pin "2") (pinfunction "2_2") (pintype "passive"))
      (node (ref "U10") (pin "7") (pinfunction "3OUTG_7") (pintype "passive"))
    )
    (net (code "167") (name "Net-(U10-3OUTR)") (class "Default")
      (node (ref "R43") (pin "2") (pinfunction "2_2") (pintype "passive"))
      (node (ref "U10") (pin "6") (pinfunction "3OUTR_6") (pintype "passive"))
    )
    (net (code "168") (name "Net-(U10-4OUTB)") (class "Default")
      (node (ref "R37") (pin "2") (pinfunction "2_2") (pintype "passive"))
      (node (ref "U10") (pin "5") (pinfunction "4OUTB_5") (pintype "passive"))
    )
    (net (code "169") (name "Net-(U10-4OUTG)") (class "Default")
      (node (ref "R32") (pin "2") (pinfunction "2_2") (pintype "passive"))
      (node (ref "U10") (pin "4") (pinfunction "4OUTG_4") (pintype "passive"))
    )
    (net (code "170") (name "Net-(U10-4OUTR)") (class "Default")
      (node (ref "R24") (pin "2") (pinfunction "2_2") (pintype "passive"))
      (node (ref "U10") (pin "3") (pinfunction "4OUTR_3") (pintype "passive"))
    )
    (net (code "171") (name "Net-(U11-1OUTB)") (class "Default")
      (node (ref "R34") (pin "1") (pinfunction "1_1") (pintype "passive"))
      (node (ref "U11") (pin "13") (pinfunction "1OUTB_13") (pintype "passive"))
    )
    (net (code "172") (name "Net-(U11-1OUTG)") (class "Default")
      (node (ref "R27") (pin "1") (pinfunction "1_1") (pintype "passive"))
      (node (ref "U11") (pin "14") (pinfunction "1OUTG_14") (pintype "passive"))
    )
    (net (code "173") (name "Net-(U11-1OUTR)") (class "Default")
      (node (ref "R20") (pin "1") (pinfunction "1_1") (pintype "passive"))
      (node (ref "U11") (pin "15") (pinfunction "1OUTR_15") (pintype "passive"))
    )
    (net (code "174") (name "Net-(U11-2OUTB)") (class "Default")
      (node (ref "R54") (pin "1") (pinfunction "1_1") (pintype "passive"))
      (node (ref "U11") (pin "10") (pinfunction "2OUTB_10") (pintype "passive"))
    )
    (net (code "175") (name "Net-(U11-2OUTG)") (class "Default")
      (node (ref "R46") (pin "1") (pinfunction "1_1") (pintype "passive"))
      (node (ref "U11") (pin "11") (pinfunction "2OUTG_11") (pintype "passive"))
    )
    (net (code "176") (name "Net-(U11-2OUTR)") (class "Default")
      (node (ref "R39") (pin "1") (pinfunction "1_1") (pintype "passive"))
      (node (ref "U11") (pin "12") (pinfunction "2OUTR_12") (pintype "passive"))
    )
    (net (code "177") (name "Net-(U11-3OUTB)") (class "Default")
      (node (ref "R59") (pin "2") (pinfunction "2_2") (pintype "passive"))
      (node (ref "U11") (pin "8") (pinfunction "3OUTB_8") (pintype "passive"))
    )
    (net (code "178") (name "Net-(U11-3OUTG)") (class "Default")
      (node (ref "R53") (pin "2") (pinfunction "2_2") (pintype "passive"))
      (node (ref "U11") (pin "7") (pinfunction "3OUTG_7") (pintype "passive"))
    )
    (net (code "179") (name "Net-(U11-3OUTR)") (class "Default")
      (node (ref "R45") (pin "2") (pinfunction "2_2") (pintype "passive"))
      (node (ref "U11") (pin "6") (pinfunction "3OUTR_6") (pintype "passive"))
    )
    (net (code "180") (name "Net-(U11-4OUTR)") (class "Default")
      (node (ref "R26") (pin "2") (pinfunction "2_2") (pintype "passive"))
      (node (ref "U11") (pin "3") (pinfunction "4OUTR_3") (pintype "passive"))
    )
    (net (code "181") (name "Net-(U12-1OUTB)") (class "Default")
      (node (ref "R35") (pin "1") (pinfunction "1_1") (pintype "passive"))
      (node (ref "U12") (pin "13") (pinfunction "1OUTB_13") (pintype "passive"))
    )
    (net (code "182") (name "Net-(U12-1OUTG)") (class "Default")
      (node (ref "R29") (pin "1") (pinfunction "1_1") (pintype "passive"))
      (node (ref "U12") (pin "14") (pinfunction "1OUTG_14") (pintype "passive"))
    )
    (net (code "183") (name "Net-(U12-1OUTR)") (class "Default")
      (node (ref "R21") (pin "1") (pinfunction "1_1") (pintype "passive"))
      (node (ref "U12") (pin "15") (pinfunction "1OUTR_15") (pintype "passive"))
    )
    (net (code "184") (name "Net-(U12-2OUTB)") (class "Default")
      (node (ref "R56") (pin "1") (pinfunction "1_1") (pintype "passive"))
      (node (ref "U12") (pin "10") (pinfunction "2OUTB_10") (pintype "passive"))
    )
    (net (code "185") (name "Net-(U12-2OUTG)") (class "Default")
      (node (ref "R48") (pin "1") (pinfunction "1_1") (pintype "passive"))
      (node (ref "U12") (pin "11") (pinfunction "2OUTG_11") (pintype "passive"))
    )
    (net (code "186") (name "Net-(U12-2OUTR)") (class "Default")
      (node (ref "R40") (pin "1") (pinfunction "1_1") (pintype "passive"))
      (node (ref "U12") (pin "12") (pinfunction "2OUTR_12") (pintype "passive"))
    )
    (net (code "187") (name "Net-(U12-3OUTB)") (class "Default")
      (node (ref "R60") (pin "2") (pinfunction "2_2") (pintype "passive"))
      (node (ref "U12") (pin "8") (pinfunction "3OUTB_8") (pintype "passive"))
    )
    (net (code "188") (name "Net-(U12-3OUTG)") (class "Default")
      (node (ref "R55") (pin "2") (pinfunction "2_2") (pintype "passive"))
      (node (ref "U12") (pin "7") (pinfunction "3OUTG_7") (pintype "passive"))
    )
    (net (code "189") (name "Net-(U12-3OUTR)") (class "Default")
      (node (ref "R47") (pin "2") (pinfunction "2_2") (pintype "passive"))
      (node (ref "U12") (pin "6") (pinfunction "3OUTR_6") (pintype "passive"))
    )
    (net (code "190") (name "Net-(U12-4OUTR)") (class "Default")
      (node (ref "R28") (pin "2") (pinfunction "2_2") (pintype "passive"))
      (node (ref "U12") (pin "3") (pinfunction "4OUTR_3") (pintype "passive"))
    )
    (net (code "191") (name "VH") (class "Default")
      (node (ref "C10") (pin "1") (pinfunction "1_1") (pintype "passive"))
      (node (ref "D2") (pin "2") (pinfunction "K_2") (pintype "passive"))
      (node (ref "J2") (pin "1") (pinfunction "1_1") (pintype "passive"))
      (node (ref "R12") (pin "2") (pinfunction "2_2") (pintype "passive"))
      (node (ref "R13") (pin "2") (pinfunction "2_2") (pintype "passive"))
      (node (ref "R4") (pin "2") (pinfunction "2_2") (pintype "passive"))
      (node (ref "R5") (pin "2") (pinfunction "2_2") (pintype "passive"))
      (node (ref "R6") (pin "1") (pinfunction "TOP_1") (pintype "passive"))
      (node (ref "R6") (pin "2") (pinfunction "TAP_2") (pintype "passive"))
      (node (ref "R7") (pin "2") (pinfunction "2_2") (pintype "passive"))
      (node (ref "R9") (pin "2") (pinfunction "2_2") (pintype "passive"))
    )
    (net (code "192") (name "unconnected-(T1-Pad1)") (class "Default")
      (node (ref "T1") (pin "1") (pinfunction "1_1") (pintype "passive"))
    )
    (net (code "193") (name "unconnected-(T2-Pad1)") (class "Default")
      (node (ref "T2") (pin "1") (pinfunction "1_1") (pintype "passive"))
    )
    (net (code "194") (name "unconnected-(T3-Pad1)") (class "Default")
      (node (ref "T3") (pin "1") (pinfunction "1_1") (pintype "passive"))
    )
    (net (code "195") (name "unconnected-(T4-Pad1)") (class "Default")
      (node (ref "T4") (pin "1") (pinfunction "1_1") (pintype "passive"))
    )
    (net (code "196") (name "unconnected-(T5-NC-Pad1)") (class "Default")
      (node (ref "T5") (pin "1") (pinfunction "NC_1") (pintype "passive"))
    )
    (net (code "197") (name "unconnected-(T5-NC-Pad8)") (class "Default")
      (node (ref "T5") (pin "8") (pinfunction "NC_8") (pintype "passive"))
    )
    (net (code "198") (name "unconnected-(T6-NC-Pad1)") (class "Default")
      (node (ref "T6") (pin "1") (pinfunction "NC_1") (pintype "passive"))
    )
    (net (code "199") (name "unconnected-(T6-NC-Pad8)") (class "Default")
      (node (ref "T6") (pin "8") (pinfunction "NC_8") (pintype "passive"))
    )
    (net (code "200") (name "unconnected-(T7-NC-Pad1)") (class "Default")
      (node (ref "T7") (pin "1") (pinfunction "NC_1") (pintype "passive"))
    )
    (net (code "201") (name "unconnected-(T7-NC-Pad8)") (class "Default")
      (node (ref "T7") (pin "8") (pinfunction "NC_8") (pintype "passive"))
    )
    (net (code "202") (name "unconnected-(T8-NC-Pad1)") (class "Default")
      (node (ref "T8") (pin "1") (pinfunction "NC_1") (pintype "passive"))
    )
    (net (code "203") (name "unconnected-(T8-NC-Pad8)") (class "Default")
      (node (ref "T8") (pin "8") (pinfunction "NC_8") (pintype "passive"))
    )
    (net (code "204") (name "unconnected-(U5-DO-Pad2)") (class "Default")
      (node (ref "U5") (pin "2") (pinfunction "DO_2") (pintype "passive"))
    )
    (net (code "205") (name "unconnected-(U7A-PA5-Pad21)") (class "Default")
      (node (ref "U7") (pin "21") (pinfunction "PA5_21") (pintype "bidirectional"))
    )
    (net (code "206") (name "unconnected-(U7A-PA8-Pad41)") (class "Default")
      (node (ref "U7") (pin "41") (pinfunction "PA8_41") (pintype "bidirectional"))
    )
    (net (code "207") (name "unconnected-(U7A-PA11-Pad44)") (class "Default")
      (node (ref "U7") (pin "44") (pinfunction "PA11_44") (pintype "bidirectional"))
    )
    (net (code "208") (name "unconnected-(U7A-PA12-Pad45)") (class "Default")
      (node (ref "U7") (pin "45") (pinfunction "PA12_45") (pintype "bidirectional"))
    )
    (net (code "209") (name "unconnected-(U7A-PA15-Pad50)") (class "Default")
      (node (ref "U7") (pin "50") (pinfunction "PA15_50") (pintype "bidirectional"))
    )
    (net (code "210") (name "unconnected-(U7A-PB5-Pad57)") (class "Default")
      (node (ref "U7") (pin "57") (pinfunction "PB5_57") (pintype "bidirectional"))
    )
    (net (code "211") (name "unconnected-(U7A-PB9-Pad62)") (class "Default")
      (node (ref "U7") (pin "62") (pinfunction "PB9_62") (pintype "bidirectional"))
    )
    (net (code "212") (name "unconnected-(U7A-PB10-Pad29)") (class "Default")
      (node (ref "U7") (pin "29") (pinfunction "PB10_29") (pintype "bidirectional"))
    )
    (net (code "213") (name "unconnected-(U7A-PB11-Pad30)") (class "Default")
      (node (ref "U7") (pin "30") (pinfunction "PB11_30") (pintype "bidirectional"))
    )
    (net (code "214") (name "unconnected-(U7A-PB12-Pad33)") (class "Default")
      (node (ref "U7") (pin "33") (pinfunction "PB12_33") (pintype "bidirectional"))
    )
    (net (code "215") (name "unconnected-(U7A-PB13-Pad34)") (class "Default")
      (node (ref "U7") (pin "34") (pinfunction "PB13_34") (pintype "bidirectional"))
    )
    (net (code "216") (name "unconnected-(U7A-PB14-Pad35)") (class "Default")
      (node (ref "U7") (pin "35") (pinfunction "PB14_35") (pintype "bidirectional"))
    )
    (net (code "217") (name "unconnected-(U7A-PC4-Pad24)") (class "Default")
      (node (ref "U7") (pin "24") (pinfunction "PC4_24") (pintype "bidirectional"))
    )
    (net (code "218") (name "unconnected-(U7A-PC5-Pad25)") (class "Default")
      (node (ref "U7") (pin "25") (pinfunction "PC5_25") (pintype "bidirectional"))
    )
    (net (code "219") (name "unconnected-(U7A-PC6-Pad37)") (class "Default")
      (node (ref "U7") (pin "37") (pinfunction "PC6_37") (pintype "bidirectional"))
    )
    (net (code "220") (name "unconnected-(U7A-PC7-Pad38)") (class "Default")
      (node (ref "U7") (pin "38") (pinfunction "PC7_38") (pintype "bidirectional"))
    )
    (net (code "221") (name "unconnected-(U7A-PC8-Pad39)") (class "Default")
      (node (ref "U7") (pin "39") (pinfunction "PC8_39") (pintype "bidirectional"))
    )
    (net (code "222") (name "unconnected-(U7A-PC9-Pad40)") (class "Default")
      (node (ref "U7") (pin "40") (pinfunction "PC9_40") (pintype "bidirectional"))
    )
    (net (code "223") (name "unconnected-(U7A-PC10-Pad51)") (class "Default")
      (node (ref "U7") (pin "51") (pinfunction "PC10_51") (pintype "bidirectional"))
    )
    (net (code "224") (name "unconnected-(U7A-PC11-Pad52)") (class "Default")
      (node (ref "U7") (pin "52") (pinfunction "PC11_52") (pintype "bidirectional"))
    )
    (net (code "225") (name "unconnected-(U7A-PC12-Pad53)") (class "Default")
      (node (ref "U7") (pin "53") (pinfunction "PC12_53") (pintype "bidirectional"))
    )
    (net (code "226") (name "unconnected-(U7A-PC13-TAMPER-RTC-Pad2)") (class "Default")
      (node (ref "U7") (pin "2") (pinfunction "PC13-TAMPER-RTC_2") (pintype "bidirectional"))
    )
    (net (code "227") (name "unconnected-(U7A-PC14-OSC32_IN-Pad3)") (class "Default")
      (node (ref "U7") (pin "3") (pinfunction "PC14-OSC32_IN_3") (pintype "bidirectional"))
    )
    (net (code "228") (name "unconnected-(U7A-PC15-OSC32_OUT-Pad4)") (class "Default")
      (node (ref "U7") (pin "4") (pinfunction "PC15-OSC32_OUT_4") (pintype "bidirectional"))
    )
    (net (code "229") (name "unconnected-(U7A-PD2-Pad54)") (class "Default")
      (node (ref "U7") (pin "54") (pinfunction "PD2_54") (pintype "bidirectional"))
    )
    (net (code "230") (name "unconnected-(U8-CTS#-Pad9)") (class "Default")
      (node (ref "U8") (pin "9") (pinfunction "CTS#_9") (pintype "passive"))
    )
    (net (code "231") (name "unconnected-(U8-DCD#-Pad13)") (class "Default")
      (node (ref "U8") (pin "13") (pinfunction "DCD#_13") (pintype "passive"))
    )
    (net (code "232") (name "unconnected-(U8-DSR#-Pad15)") (class "Default")
      (node (ref "U8") (pin "15") (pinfunction "DSR#_15") (pintype "passive"))
    )
    (net (code "233") (name "unconnected-(U8-R232-Pad10)") (class "Default")
      (node (ref "U8") (pin "10") (pinfunction "R232_10") (pintype "passive"))
    )
    (net (code "234") (name "unconnected-(U8-RI#-Pad14)") (class "Default")
      (node (ref "U8") (pin "14") (pinfunction "RI#_14") (pintype "passive"))
    )
    (net (code "235") (name "unconnected-(U9-4OUTB-Pad5)") (class "Default")
      (node (ref "U9") (pin "5") (pinfunction "4OUTB_5") (pintype "passive"))
    )
    (net (code "236") (name "unconnected-(U9-4OUTG-Pad4)") (class "Default")
      (node (ref "U9") (pin "4") (pinfunction "4OUTG_4") (pintype "passive"))
    )
    (net (code "237") (name "unconnected-(U9-DOUT-Pad2)") (class "Default")
      (node (ref "U9") (pin "2") (pinfunction "DOUT_2") (pintype "passive"))
    )
    (net (code "238") (name "unconnected-(U10-DOUT-Pad2)") (class "Default")
      (node (ref "U10") (pin "2") (pinfunction "DOUT_2") (pintype "passive"))
    )
    (net (code "239") (name "unconnected-(U11-4OUTB-Pad5)") (class "Default")
      (node (ref "U11") (pin "5") (pinfunction "4OUTB_5") (pintype "passive"))
    )
    (net (code "240") (name "unconnected-(U11-4OUTG-Pad4)") (class "Default")
      (node (ref "U11") (pin "4") (pinfunction "4OUTG_4") (pintype "passive"))
    )
    (net (code "241") (name "unconnected-(U11-DOUT-Pad2)") (class "Default")
      (node (ref "U11") (pin "2") (pinfunction "DOUT_2") (pintype "passive"))
    )
    (net (code "242") (name "unconnected-(U12-4OUTB-Pad5)") (class "Default")
      (node (ref "U12") (pin "5") (pinfunction "4OUTB_5") (pintype "passive"))
    )
    (net (code "243") (name "unconnected-(U12-4OUTG-Pad4)") (class "Default")
      (node (ref "U12") (pin "4") (pinfunction "4OUTG_4") (pintype "passive"))
    )
    (net (code "244") (name "unconnected-(U12-DOUT-Pad2)") (class "Default")
      (node (ref "U12") (pin "2") (pinfunction "DOUT_2") (pintype "passive"))
    )
    (net (code "245") (name "unconnected-(U14-32KHZ-Pad1)") (class "Default")
      (node (ref "U14") (pin "1") (pinfunction "32KHZ_1") (pintype "passive"))
    )
    (net (code "246") (name "unconnected-(U14-~{RST}-Pad4)") (class "Default")
      (node (ref "U14") (pin "4") (pinfunction "~{RST}_4") (pintype "passive"))
    )
  )
)
